# watchplb_mainboard_v1_1.net
KiCad netlist of a schematic drawn in EAGLE
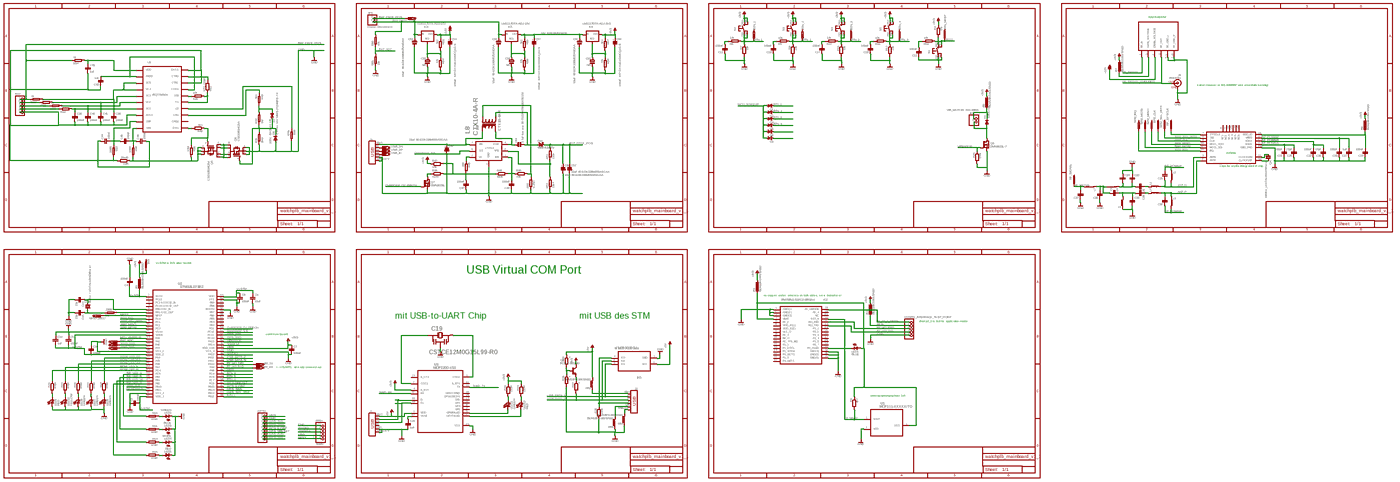
[diagram p0: schematic, sheet 1, overview]
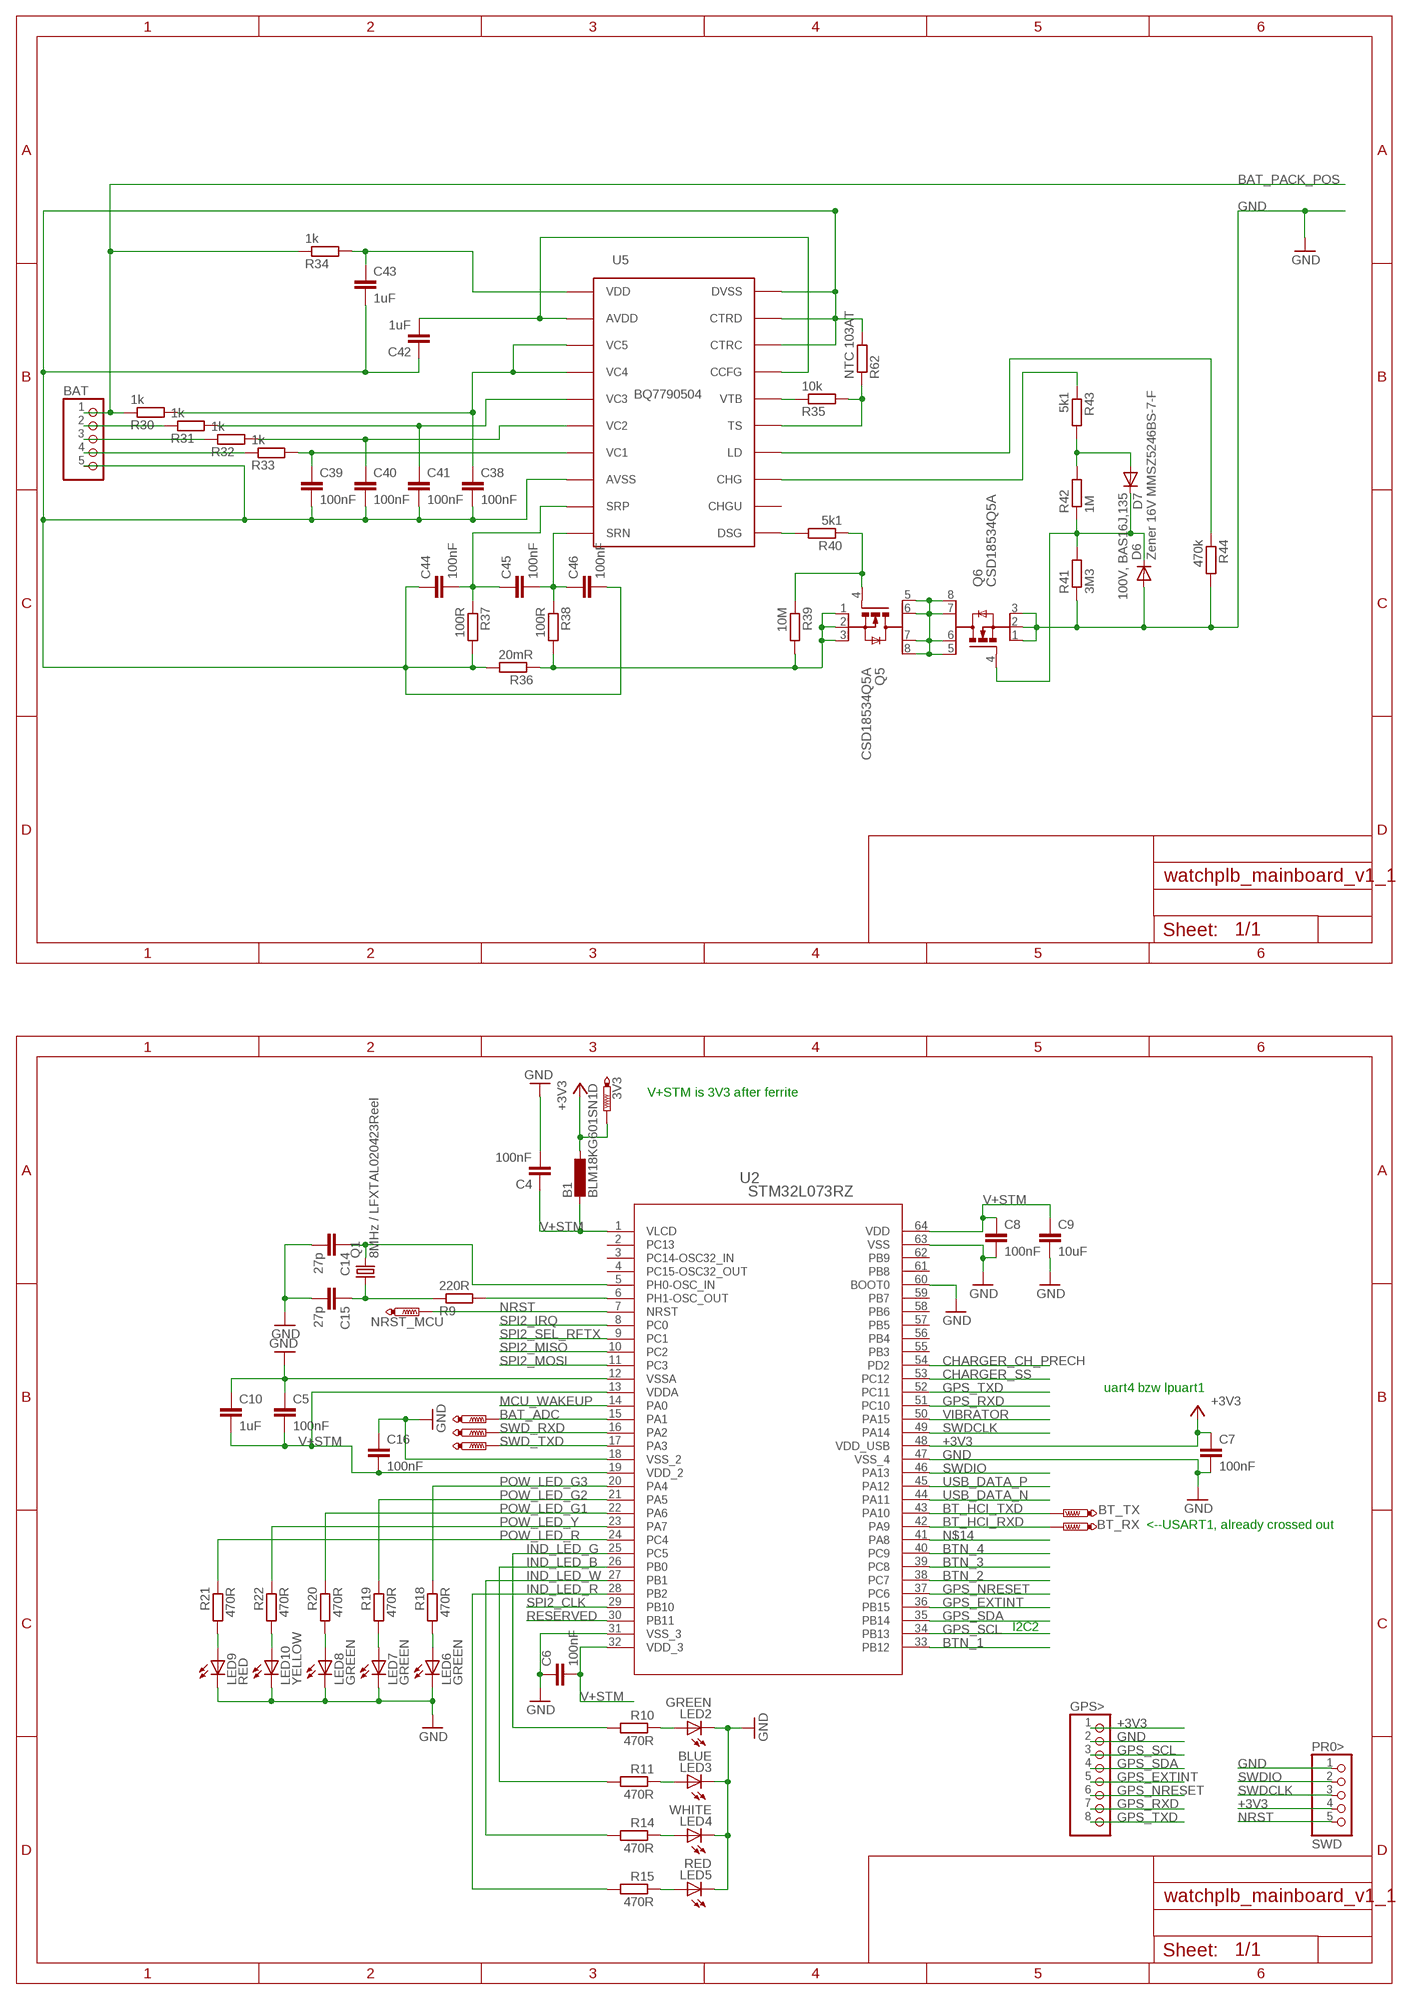
[diagram p1: schematic, sheet 1, part 1 of 4]
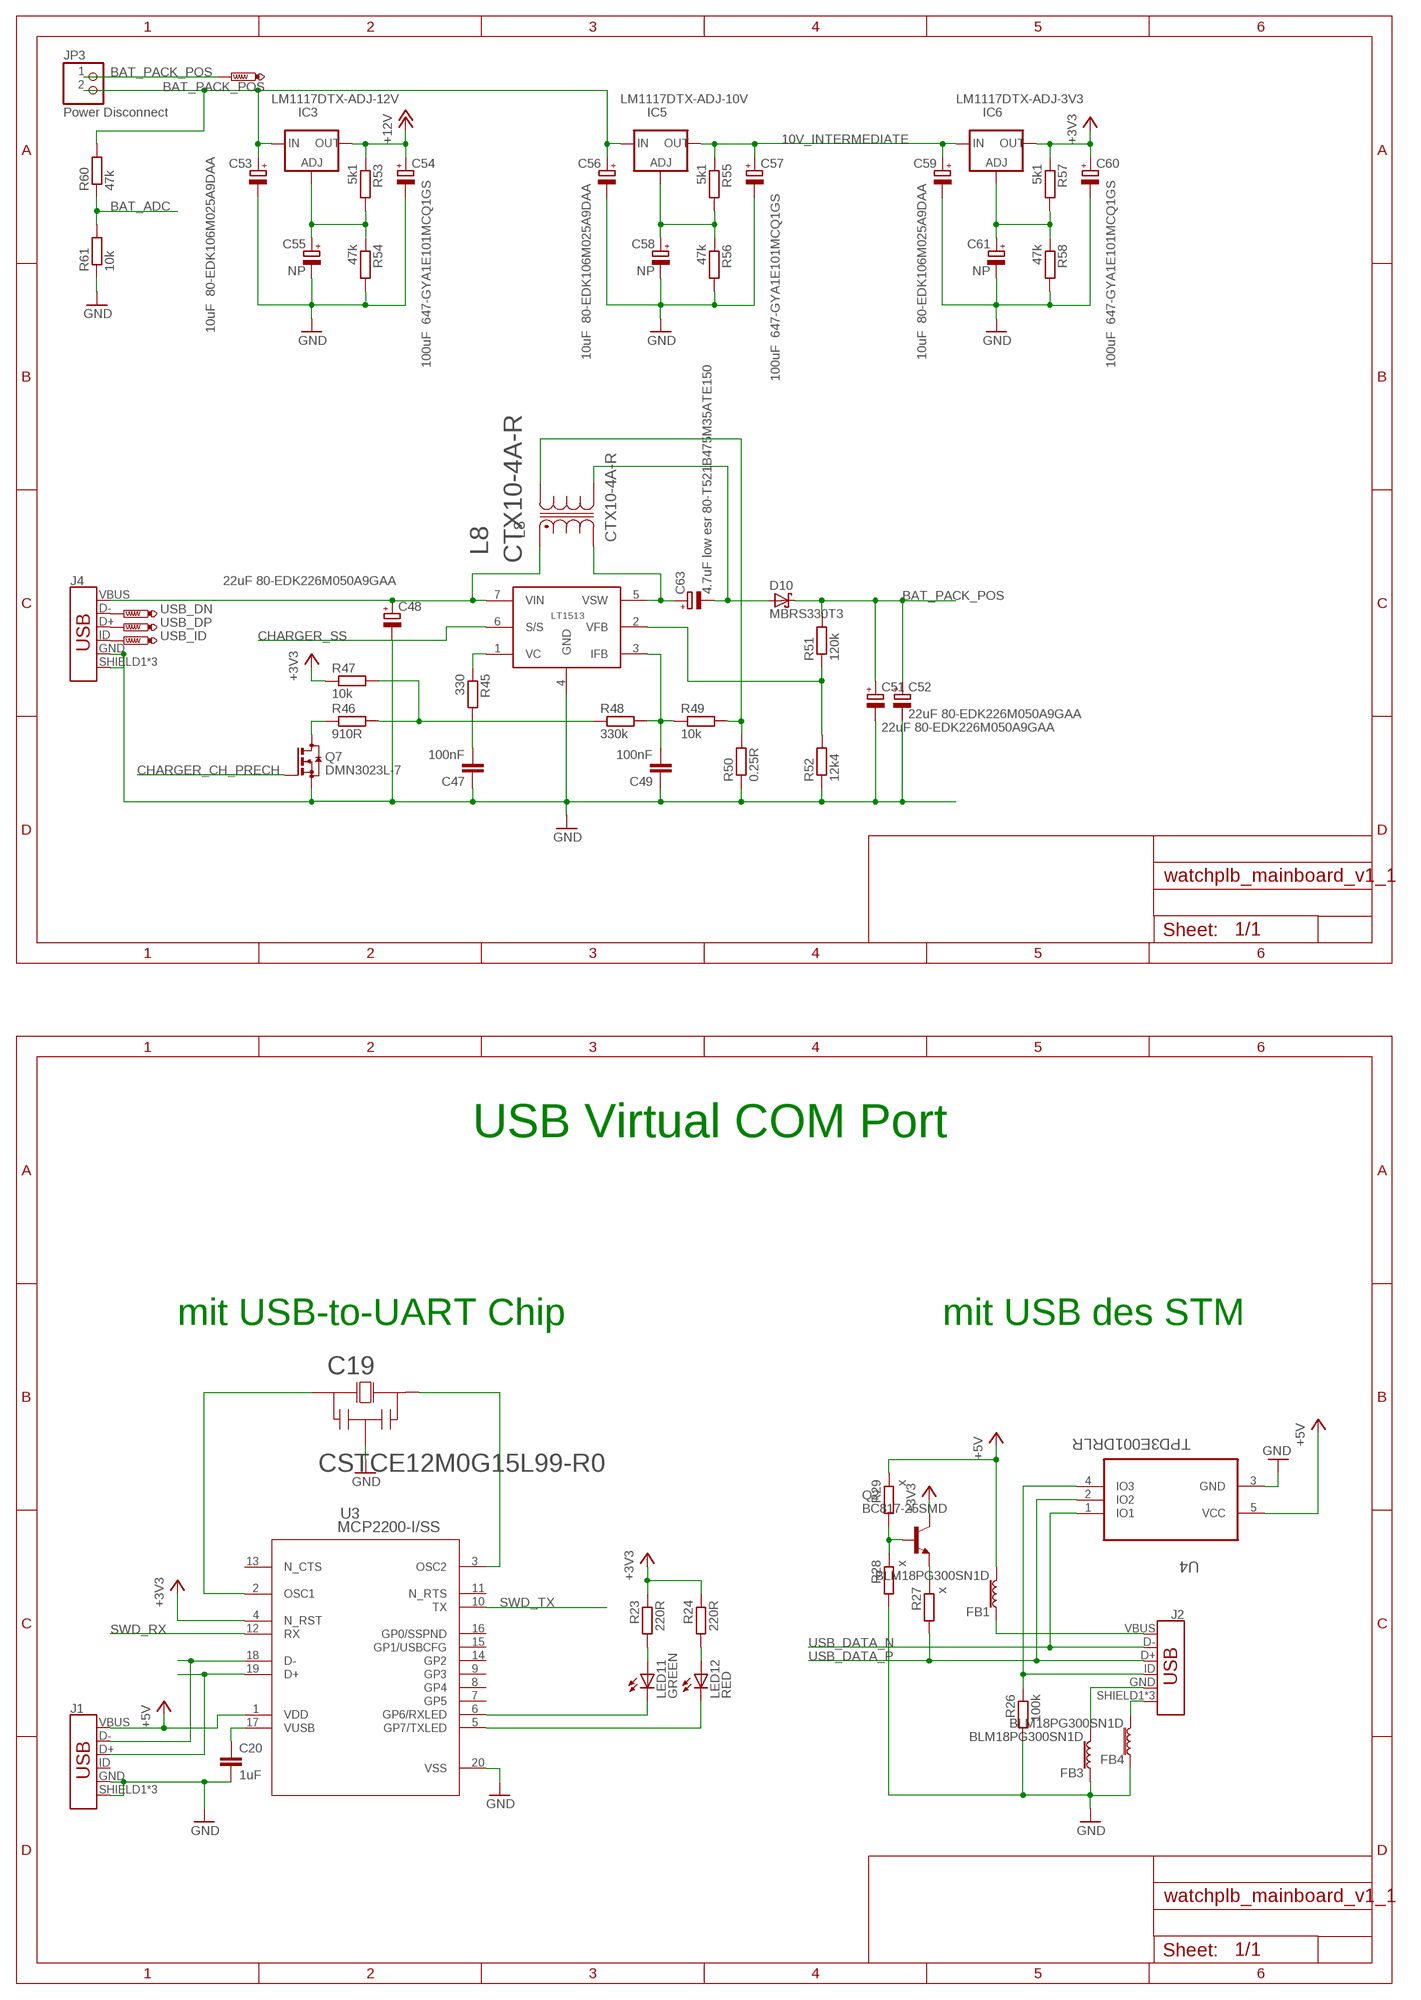
[diagram p2: schematic, sheet 1, part 2 of 4]
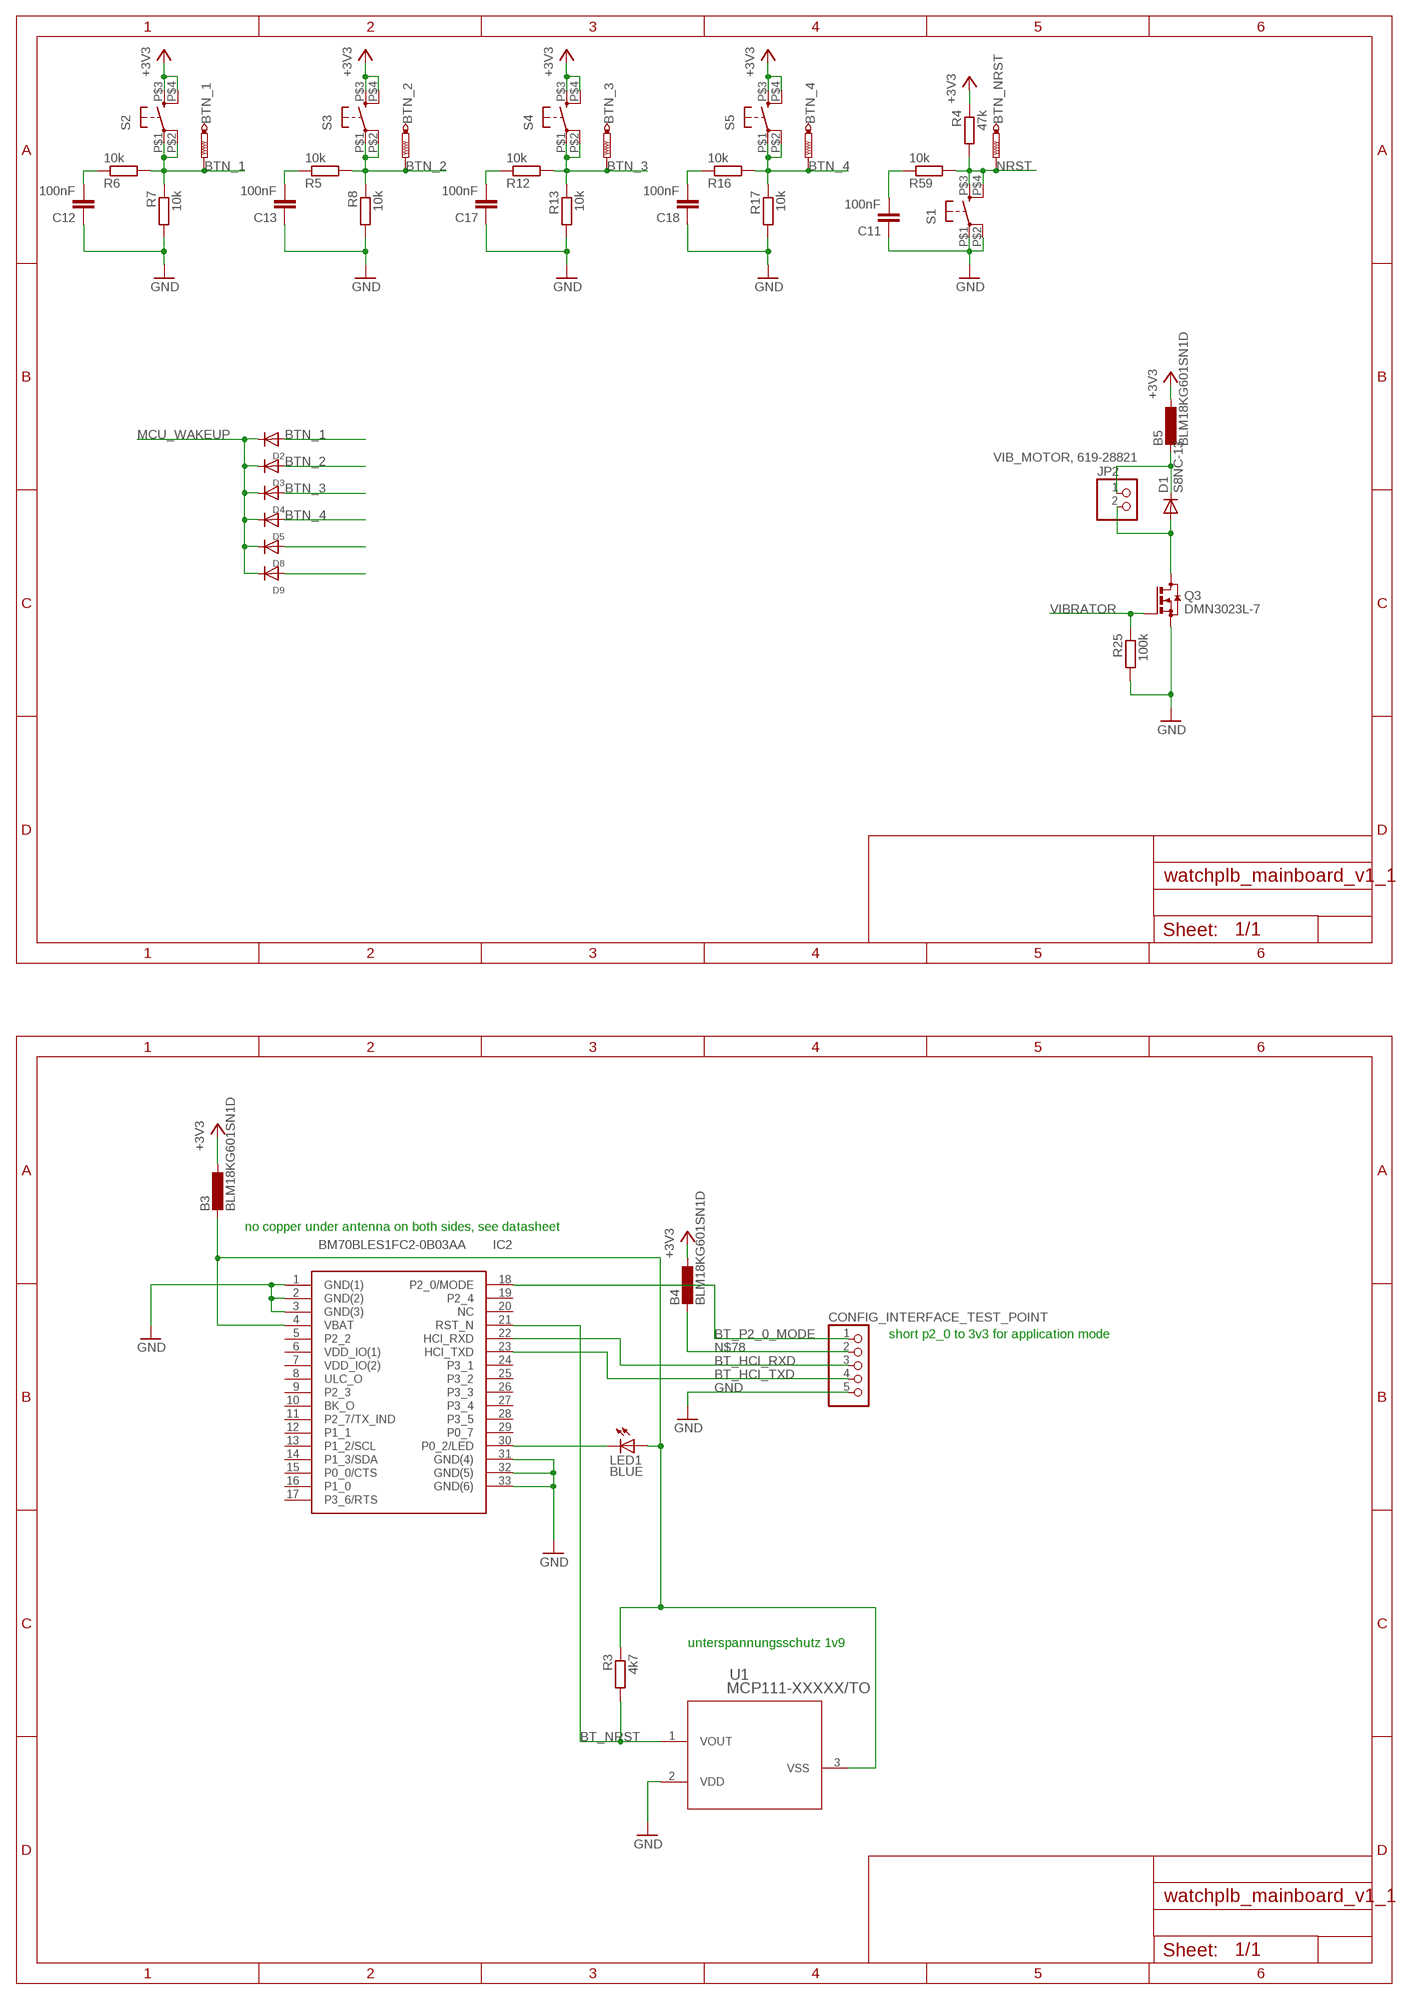
[diagram p3: schematic, sheet 1, part 3 of 4]
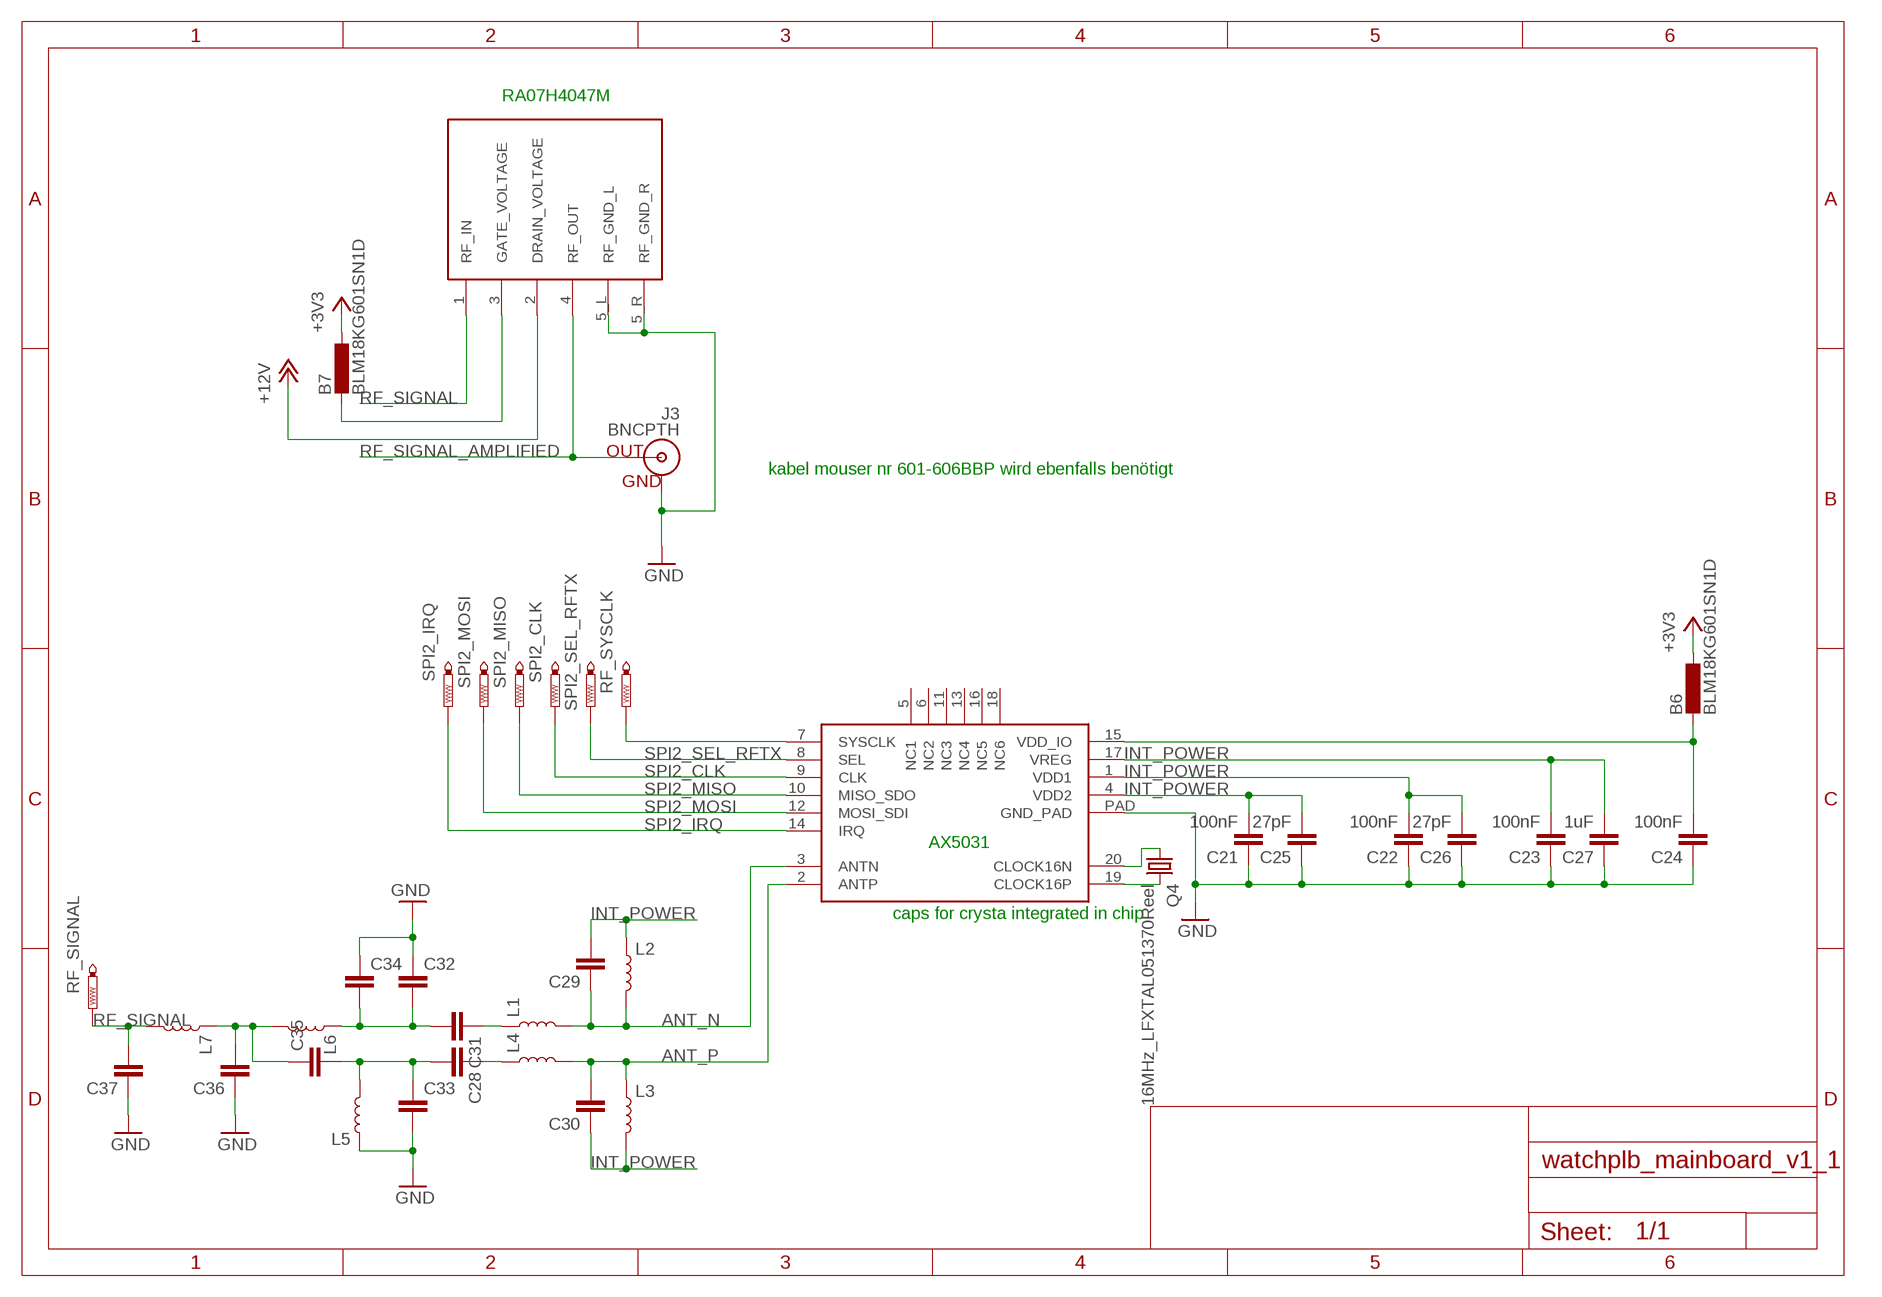
[diagram p4: schematic, sheet 1, part 4 of 4]

(export (version "E")
  (design (tool "Eeschema 10.0.6"))
  (components
    (comp (ref "3V3")
      (value "PTR1B1,27")
      (footprint "eagle-import:B1,27")
      (libsource (lib "eagle-import") (part "PTR1B1,27"))
    )
    (comp (ref "B1")
      (value "BLM18KG601SN1D")
      (footprint "eagle-import:L0603")
      (libsource (lib "eagle-import") (part "B-EU_B0603"))
    )
    (comp (ref "B3")
      (value "BLM18KG601SN1D")
      (footprint "eagle-import:L0603")
      (libsource (lib "eagle-import") (part "B-EU_B0603"))
    )
    (comp (ref "B4")
      (value "BLM18KG601SN1D")
      (footprint "eagle-import:L0603")
      (libsource (lib "eagle-import") (part "B-EU_B0603"))
    )
    (comp (ref "B5")
      (value "BLM18KG601SN1D")
      (footprint "eagle-import:L0603")
      (libsource (lib "eagle-import") (part "B-EU_B0603"))
    )
    (comp (ref "B6")
      (value "BLM18KG601SN1D")
      (footprint "eagle-import:L0603")
      (libsource (lib "eagle-import") (part "B-EU_B0603"))
    )
    (comp (ref "B7")
      (value "BLM18KG601SN1D")
      (footprint "eagle-import:L0603")
      (libsource (lib "eagle-import") (part "B-EU_B0603"))
    )
    (comp (ref "BAT")
      (value "PINHD-1X5")
      (footprint "eagle-import:1X05")
      (libsource (lib "eagle-import") (part "PINHD-1X5"))
    )
    (comp (ref "BAT_ADC")
      (value "PTR1B1,27")
      (footprint "eagle-import:B1,27")
      (libsource (lib "eagle-import") (part "PTR1B1,27"))
    )
    (comp (ref "BAT_PACK_POS")
      (value "PTR1B2,54")
      (footprint "eagle-import:B2,54")
      (libsource (lib "eagle-import") (part "PTR1B2,54"))
    )
    (comp (ref "BTN_1")
      (value "PTR1B1,27")
      (footprint "eagle-import:B1,27")
      (libsource (lib "eagle-import") (part "PTR1B1,27"))
    )
    (comp (ref "BTN_2")
      (value "PTR1B1,27")
      (footprint "eagle-import:B1,27")
      (libsource (lib "eagle-import") (part "PTR1B1,27"))
    )
    (comp (ref "BTN_3")
      (value "PTR1B1,27")
      (footprint "eagle-import:B1,27")
      (libsource (lib "eagle-import") (part "PTR1B1,27"))
    )
    (comp (ref "BTN_4")
      (value "PTR1B1,27")
      (footprint "eagle-import:B1,27")
      (libsource (lib "eagle-import") (part "PTR1B1,27"))
    )
    (comp (ref "BTN_NRST")
      (value "PTR1B1,27")
      (footprint "eagle-import:B1,27")
      (libsource (lib "eagle-import") (part "PTR1B1,27"))
    )
    (comp (ref "BT_RX")
      (value "PTR1B1,27")
      (footprint "eagle-import:B1,27")
      (libsource (lib "eagle-import") (part "PTR1B1,27"))
    )
    (comp (ref "BT_TX")
      (value "PTR1B1,27")
      (footprint "eagle-import:B1,27")
      (libsource (lib "eagle-import") (part "PTR1B1,27"))
    )
    (comp (ref "C4")
      (value "100nF")
      (footprint "eagle-import:C0805")
      (libsource (lib "eagle-import") (part "C-EUC0805"))
    )
    (comp (ref "C5")
      (value "100nF")
      (footprint "eagle-import:C0805")
      (libsource (lib "eagle-import") (part "C-EUC0805"))
    )
    (comp (ref "C6")
      (value "100nF")
      (footprint "eagle-import:C0805")
      (libsource (lib "eagle-import") (part "C-EUC0805"))
    )
    (comp (ref "C7")
      (value "100nF")
      (footprint "eagle-import:C0805")
      (libsource (lib "eagle-import") (part "C-EUC0805"))
    )
    (comp (ref "C8")
      (value "100nF")
      (footprint "eagle-import:C0805")
      (libsource (lib "eagle-import") (part "C-EUC0805"))
    )
    (comp (ref "C9")
      (value "10uF")
      (footprint "eagle-import:C1206")
      (libsource (lib "eagle-import") (part "C-EUC1206"))
    )
    (comp (ref "C10")
      (value "1uF")
      (footprint "eagle-import:C0805")
      (libsource (lib "eagle-import") (part "C-EUC0805"))
    )
    (comp (ref "C11")
      (value "100nF")
      (footprint "eagle-import:C0805")
      (libsource (lib "eagle-import") (part "C-EUC0805"))
    )
    (comp (ref "C12")
      (value "100nF")
      (footprint "eagle-import:C0805")
      (libsource (lib "eagle-import") (part "C-EUC0805"))
    )
    (comp (ref "C13")
      (value "100nF")
      (footprint "eagle-import:C0805")
      (libsource (lib "eagle-import") (part "C-EUC0805"))
    )
    (comp (ref "C14")
      (value "27p")
      (footprint "eagle-import:C0805")
      (libsource (lib "eagle-import") (part "C-EUC0805"))
    )
    (comp (ref "C15")
      (value "27p")
      (footprint "eagle-import:C0805")
      (libsource (lib "eagle-import") (part "C-EUC0805"))
    )
    (comp (ref "C16")
      (value "100nF")
      (footprint "eagle-import:C0805")
      (libsource (lib "eagle-import") (part "C-EUC0805"))
    )
    (comp (ref "C17")
      (value "100nF")
      (footprint "eagle-import:C0805")
      (libsource (lib "eagle-import") (part "C-EUC0805"))
    )
    (comp (ref "C18")
      (value "100nF")
      (footprint "eagle-import:C0805")
      (libsource (lib "eagle-import") (part "C-EUC0805"))
    )
    (comp (ref "C19")
      (value "CSTCE12M0G15L99-R0")
      (footprint "eagle-import:CSTCE")
      (fields (field (name "MANUFACTURER_PART_NUMBER") "CSTCE8M00G52R0"))
      (libsource (lib "eagle-import") (part "CSTCE8M00G52-R0"))
    )
    (comp (ref "C20")
      (value "1uF")
      (footprint "eagle-import:C0805")
      (libsource (lib "eagle-import") (part "C-EUC0805"))
    )
    (comp (ref "C21")
      (value "100nF")
      (footprint "eagle-import:C0805")
      (libsource (lib "eagle-import") (part "C-EUC0805"))
    )
    (comp (ref "C22")
      (value "100nF")
      (footprint "eagle-import:C0805")
      (libsource (lib "eagle-import") (part "C-EUC0805"))
    )
    (comp (ref "C23")
      (value "100nF")
      (footprint "eagle-import:C0805")
      (libsource (lib "eagle-import") (part "C-EUC0805"))
    )
    (comp (ref "C24")
      (value "100nF")
      (footprint "eagle-import:C0805")
      (libsource (lib "eagle-import") (part "C-EUC0805"))
    )
    (comp (ref "C25")
      (value "27pF")
      (footprint "eagle-import:C0805")
      (libsource (lib "eagle-import") (part "C-EUC0805"))
    )
    (comp (ref "C26")
      (value "27pF")
      (footprint "eagle-import:C0805")
      (libsource (lib "eagle-import") (part "C-EUC0805"))
    )
    (comp (ref "C27")
      (value "1uF")
      (footprint "eagle-import:C0805")
      (libsource (lib "eagle-import") (part "C-EUC0805"))
    )
    (comp (ref "C28")
      (value "C-EUC0805")
      (footprint "eagle-import:C0805")
      (libsource (lib "eagle-import") (part "C-EUC0805"))
    )
    (comp (ref "C29")
      (value "C-EUC0805")
      (footprint "eagle-import:C0805")
      (libsource (lib "eagle-import") (part "C-EUC0805"))
    )
    (comp (ref "C30")
      (value "C-EUC0805")
      (footprint "eagle-import:C0805")
      (libsource (lib "eagle-import") (part "C-EUC0805"))
    )
    (comp (ref "C31")
      (value "C-EUC0805")
      (footprint "eagle-import:C0805")
      (libsource (lib "eagle-import") (part "C-EUC0805"))
    )
    (comp (ref "C32")
      (value "C-EUC0805")
      (footprint "eagle-import:C0805")
      (libsource (lib "eagle-import") (part "C-EUC0805"))
    )
    (comp (ref "C33")
      (value "C-EUC0805")
      (footprint "eagle-import:C0805")
      (libsource (lib "eagle-import") (part "C-EUC0805"))
    )
    (comp (ref "C34")
      (value "C-EUC0805")
      (footprint "eagle-import:C0805")
      (libsource (lib "eagle-import") (part "C-EUC0805"))
    )
    (comp (ref "C35")
      (value "C-EUC0805")
      (footprint "eagle-import:C0805")
      (libsource (lib "eagle-import") (part "C-EUC0805"))
    )
    (comp (ref "C36")
      (value "C-EUC0805")
      (footprint "eagle-import:C0805")
      (libsource (lib "eagle-import") (part "C-EUC0805"))
    )
    (comp (ref "C37")
      (value "C-EUC0805")
      (footprint "eagle-import:C0805")
      (libsource (lib "eagle-import") (part "C-EUC0805"))
    )
    (comp (ref "C38")
      (value "100nF")
      (footprint "eagle-import:C0805K")
      (libsource (lib "eagle-import") (part "C-EUC0805K"))
    )
    (comp (ref "C39")
      (value "100nF")
      (footprint "eagle-import:C0805K")
      (libsource (lib "eagle-import") (part "C-EUC0805K"))
    )
    (comp (ref "C40")
      (value "100nF")
      (footprint "eagle-import:C0805K")
      (libsource (lib "eagle-import") (part "C-EUC0805K"))
    )
    (comp (ref "C41")
      (value "100nF")
      (footprint "eagle-import:C0805K")
      (libsource (lib "eagle-import") (part "C-EUC0805K"))
    )
    (comp (ref "C42")
      (value "1uF")
      (footprint "eagle-import:C0805K")
      (libsource (lib "eagle-import") (part "C-EUC0805K"))
    )
    (comp (ref "C43")
      (value "1uF")
      (footprint "eagle-import:C0805K")
      (libsource (lib "eagle-import") (part "C-EUC0805K"))
    )
    (comp (ref "C44")
      (value "100nF")
      (footprint "eagle-import:C0805K")
      (libsource (lib "eagle-import") (part "C-EUC0805K"))
    )
    (comp (ref "C45")
      (value "100nF")
      (footprint "eagle-import:C0805K")
      (libsource (lib "eagle-import") (part "C-EUC0805K"))
    )
    (comp (ref "C46")
      (value "100nF")
      (footprint "eagle-import:C0805K")
      (libsource (lib "eagle-import") (part "C-EUC0805K"))
    )
    (comp (ref "C47")
      (value "100nF")
      (footprint "eagle-import:C0805K")
      (libsource (lib "eagle-import") (part "C-EUC0805K"))
    )
    (comp (ref "C48")
      (value "22uF 80-EDK226M050A9GAA")
      (footprint "eagle-import:PANASONIC_E")
      (libsource (lib "eagle-import") (part "CPOL-EUE"))
    )
    (comp (ref "C49")
      (value "100nF")
      (footprint "eagle-import:C0805K")
      (libsource (lib "eagle-import") (part "C-EUC0805K"))
    )
    (comp (ref "C51")
      (value "22uF 80-EDK226M050A9GAA")
      (footprint "eagle-import:PANASONIC_E")
      (libsource (lib "eagle-import") (part "CPOL-EUE"))
    )
    (comp (ref "C52")
      (value "22uF 80-EDK226M050A9GAA")
      (footprint "eagle-import:PANASONIC_E")
      (libsource (lib "eagle-import") (part "CPOL-EUE"))
    )
    (comp (ref "C53")
      (value "10uF 80-EDK106M025A9DAA")
      (footprint "eagle-import:PANASONIC_E")
      (libsource (lib "eagle-import") (part "CPOL-EUE"))
    )
    (comp (ref "C54")
      (value "100uF 647-GYA1E101MCQ1GS")
      (footprint "eagle-import:PANASONIC_E")
      (libsource (lib "eagle-import") (part "CPOL-EUE"))
    )
    (comp (ref "C55")
      (value "NP")
      (footprint "eagle-import:PANASONIC_E")
      (libsource (lib "eagle-import") (part "CPOL-EUE"))
    )
    (comp (ref "C56")
      (value "10uF 80-EDK106M025A9DAA")
      (footprint "eagle-import:PANASONIC_E")
      (libsource (lib "eagle-import") (part "CPOL-EUE"))
    )
    (comp (ref "C57")
      (value "100uF 647-GYA1E101MCQ1GS")
      (footprint "eagle-import:PANASONIC_E")
      (libsource (lib "eagle-import") (part "CPOL-EUE"))
    )
    (comp (ref "C58")
      (value "NP")
      (footprint "eagle-import:PANASONIC_E")
      (libsource (lib "eagle-import") (part "CPOL-EUE"))
    )
    (comp (ref "C59")
      (value "10uF 80-EDK106M025A9DAA")
      (footprint "eagle-import:PANASONIC_E")
      (libsource (lib "eagle-import") (part "CPOL-EUE"))
    )
    (comp (ref "C60")
      (value "100uF 647-GYA1E101MCQ1GS")
      (footprint "eagle-import:PANASONIC_E")
      (libsource (lib "eagle-import") (part "CPOL-EUE"))
    )
    (comp (ref "C61")
      (value "NP")
      (footprint "eagle-import:PANASONIC_E")
      (libsource (lib "eagle-import") (part "CPOL-EUE"))
    )
    (comp (ref "C63")
      (value "4.7uF low esr 80-T521B475M35ATE150")
      (footprint "eagle-import:B_3528-21R")
      (libsource (lib "eagle-import") (part "CPOL-EUB/3528-21R"))
    )
    (comp (ref "CONFIG_INTERFACE_TEST_POINT")
      (value "PINHD-1X5")
      (footprint "eagle-import:1X05")
      (libsource (lib "eagle-import") (part "PINHD-1X5"))
    )
    (comp (ref "D1")
      (value "S8NC-13")
      (footprint "eagle-import:SMC")
      (libsource (lib "eagle-import") (part "DIODE-SMC"))
    )
    (comp (ref "D2")
      (value "DIODESOD-123")
      (footprint "eagle-import:SOD-123")
      (libsource (lib "eagle-import") (part "DIODESOD-123"))
    )
    (comp (ref "D3")
      (value "DIODESOD-123")
      (footprint "eagle-import:SOD-123")
      (libsource (lib "eagle-import") (part "DIODESOD-123"))
    )
    (comp (ref "D4")
      (value "DIODESOD-123")
      (footprint "eagle-import:SOD-123")
      (libsource (lib "eagle-import") (part "DIODESOD-123"))
    )
    (comp (ref "D5")
      (value "DIODESOD-123")
      (footprint "eagle-import:SOD-123")
      (libsource (lib "eagle-import") (part "DIODESOD-123"))
    )
    (comp (ref "D6")
      (value "Zener 16V MMSZ5246BS-7-F")
      (footprint "eagle-import:SOD323-R")
      (libsource (lib "eagle-import") (part "diode-1_DIODE-SOD323-R"))
    )
    (comp (ref "D7")
      (value "100V, BAS16J,135")
      (footprint "eagle-import:SOD323-R")
      (libsource (lib "eagle-import") (part "diode-1_DIODE-SOD323-R"))
    )
    (comp (ref "D8")
      (value "DIODESOD-123")
      (footprint "eagle-import:SOD-123")
      (libsource (lib "eagle-import") (part "DIODESOD-123"))
    )
    (comp (ref "D9")
      (value "DIODESOD-123")
      (footprint "eagle-import:SOD-123")
      (libsource (lib "eagle-import") (part "DIODESOD-123"))
    )
    (comp (ref "D10")
      (value "MBRS330T3")
      (footprint "eagle-import:SMC")
      (libsource (lib "eagle-import") (part "MBRS30T33"))
    )
    (comp (ref "FB1")
      (value "BLM18PG300SN1D")
      (footprint "eagle-import:0603")
      (libsource (lib "eagle-import") (part "FERRITE_BEAD-0603"))
    )
    (comp (ref "FB3")
      (value "BLM18PG300SN1D")
      (footprint "eagle-import:0603")
      (libsource (lib "eagle-import") (part "FERRITE_BEAD-0603"))
    )
    (comp (ref "FB4")
      (value "BLM18PG300SN1D")
      (footprint "eagle-import:0603")
      (libsource (lib "eagle-import") (part "FERRITE_BEAD-0603"))
    )
    (comp (ref "GPS>")
      (value "PINHD-1X8")
      (footprint "eagle-import:1X08")
      (libsource (lib "eagle-import") (part "PINHD-1X8"))
    )
    (comp (ref "IC2")
      (value "BM70BLES1FC2-0B03AA")
      (footprint "eagle-import:BM78SPPS5NC2_1")
      (libsource (lib "eagle-import") (part "BM70BLES1FC2-0B03AA"))
    )
    (comp (ref "IC3")
      (value "LM1117DTX-ADJ-12V")
      (footprint "eagle-import:TO252")
      (libsource (lib "eagle-import") (part "LM1117DTX-ADJ"))
    )
    (comp (ref "IC5")
      (value "LM1117DTX-ADJ-10V")
      (footprint "eagle-import:TO252")
      (libsource (lib "eagle-import") (part "LM1117DTX-ADJ"))
    )
    (comp (ref "IC6")
      (value "LM1117DTX-ADJ-3V3")
      (footprint "eagle-import:TO252")
      (libsource (lib "eagle-import") (part "LM1117DTX-ADJ"))
    )
    (comp (ref "J1")
      (value "USB_MICRO-B_FEMALE-SMT")
      (footprint "eagle-import:USB-B-MICRO-SMD")
      (libsource (lib "eagle-import") (part "USB_MICRO-B_FEMALE-SMT"))
    )
    (comp (ref "J2")
      (value "USB_MICRO-B_FEMALE-SMT")
      (footprint "eagle-import:USB-B-MICRO-SMD")
      (libsource (lib "eagle-import") (part "USB_MICRO-B_FEMALE-SMT"))
    )
    (comp (ref "J3")
      (value "BNCPTH")
      (footprint "eagle-import:BNC")
      (libsource (lib "eagle-import") (part "BNCPTH"))
    )
    (comp (ref "J4")
      (value "USB_MICRO-B_FEMALE-SMT")
      (footprint "eagle-import:USB-B-MICRO-SMD")
      (libsource (lib "eagle-import") (part "USB_MICRO-B_FEMALE-SMT"))
    )
    (comp (ref "JP2")
      (value "VIB_MOTOR, 619-28821")
      (footprint "eagle-import:1X02")
      (libsource (lib "eagle-import") (part "PINHD-1X2"))
    )
    (comp (ref "JP3")
      (value "Power Disconnect")
      (footprint "eagle-import:1X02")
      (libsource (lib "eagle-import") (part "PINHD-1X2"))
    )
    (comp (ref "L1")
      (value "INDUCTOR-0805-3.3UH")
      (footprint "eagle-import:0805")
      (libsource (lib "eagle-import") (part "INDUCTOR-0805-3.3UH"))
    )
    (comp (ref "L2")
      (value "INDUCTOR-0805-3.3UH")
      (footprint "eagle-import:0805")
      (libsource (lib "eagle-import") (part "INDUCTOR-0805-3.3UH"))
    )
    (comp (ref "L3")
      (value "INDUCTOR-0805-3.3UH")
      (footprint "eagle-import:0805")
      (libsource (lib "eagle-import") (part "INDUCTOR-0805-3.3UH"))
    )
    (comp (ref "L4")
      (value "INDUCTOR-0805-3.3UH")
      (footprint "eagle-import:0805")
      (libsource (lib "eagle-import") (part "INDUCTOR-0805-3.3UH"))
    )
    (comp (ref "L5")
      (value "INDUCTOR-0805-3.3UH")
      (footprint "eagle-import:0805")
      (libsource (lib "eagle-import") (part "INDUCTOR-0805-3.3UH"))
    )
    (comp (ref "L6")
      (value "INDUCTOR-0805-3.3UH")
      (footprint "eagle-import:0805")
      (libsource (lib "eagle-import") (part "INDUCTOR-0805-3.3UH"))
    )
    (comp (ref "L7")
      (value "INDUCTOR-0805-3.3UH")
      (footprint "eagle-import:0805")
      (libsource (lib "eagle-import") (part "INDUCTOR-0805-3.3UH"))
    )
    (comp (ref "L8")
      (value "CTX10-4A-R")
      (footprint "eagle-import:INDM115115X635N")
      (fields (field (name "MF") "Eaton"))
      (libsource (lib "eagle-import") (part "CTX10-4A-R"))
    )
    (comp (ref "LED1")
      (value "BLUE")
      (footprint "eagle-import:CHIP-LED0805")
      (libsource (lib "eagle-import") (part "LEDCHIP-LED0805"))
    )
    (comp (ref "LED2")
      (value "GREEN")
      (footprint "eagle-import:CHIP-LED0805")
      (libsource (lib "eagle-import") (part "LEDCHIP-LED0805"))
    )
    (comp (ref "LED3")
      (value "BLUE")
      (footprint "eagle-import:CHIP-LED0805")
      (libsource (lib "eagle-import") (part "LEDCHIP-LED0805"))
    )
    (comp (ref "LED4")
      (value "WHITE")
      (footprint "eagle-import:CHIP-LED0805")
      (libsource (lib "eagle-import") (part "LEDCHIP-LED0805"))
    )
    (comp (ref "LED5")
      (value "RED")
      (footprint "eagle-import:CHIP-LED0805")
      (libsource (lib "eagle-import") (part "LEDCHIP-LED0805"))
    )
    (comp (ref "LED6")
      (value "GREEN")
      (footprint "eagle-import:CHIP-LED0805")
      (libsource (lib "eagle-import") (part "LEDCHIP-LED0805"))
    )
    (comp (ref "LED7")
      (value "GREEN")
      (footprint "eagle-import:CHIP-LED0805")
      (libsource (lib "eagle-import") (part "LEDCHIP-LED0805"))
    )
    (comp (ref "LED8")
      (value "GREEN")
      (footprint "eagle-import:CHIP-LED0805")
      (libsource (lib "eagle-import") (part "LEDCHIP-LED0805"))
    )
    (comp (ref "LED9")
      (value "RED")
      (footprint "eagle-import:CHIP-LED0805")
      (libsource (lib "eagle-import") (part "LEDCHIP-LED0805"))
    )
    (comp (ref "LED10")
      (value "YELLOW")
      (footprint "eagle-import:CHIP-LED0805")
      (libsource (lib "eagle-import") (part "LEDCHIP-LED0805"))
    )
    (comp (ref "LED11")
      (value "GREEN")
      (footprint "eagle-import:CHIP-LED0805")
      (libsource (lib "eagle-import") (part "LEDCHIP-LED0805"))
    )
    (comp (ref "LED12")
      (value "RED")
      (footprint "eagle-import:CHIP-LED0805")
      (libsource (lib "eagle-import") (part "LEDCHIP-LED0805"))
    )
    (comp (ref "NRST_MCU")
      (value "PTR1B1,27")
      (footprint "eagle-import:B1,27")
      (libsource (lib "eagle-import") (part "PTR1B1,27"))
    )
    (comp (ref "PR0>")
      (value "SWD")
      (footprint "eagle-import:1X05")
      (libsource (lib "eagle-import") (part "PINHD-1X5"))
    )
    (comp (ref "Q1")
      (value "8MHz / LFXTAL020423Reel")
      (footprint "eagle-import:HC49UP")
      (libsource (lib "eagle-import") (part "crystal_CRYSTALHC49UP"))
    )
    (comp (ref "Q2")
      (value "BC817-25SMD")
      (footprint "eagle-import:SOT23-BEC")
      (libsource (lib "eagle-import") (part "BC817SMD-25"))
    )
    (comp (ref "Q3")
      (value "DMN3023L-7")
      (footprint "eagle-import:SOT23")
      (libsource (lib "eagle-import") (part "BSS123"))
    )
    (comp (ref "Q4")
      (value "16MHz_LFXTAL051370Reel")
      (footprint "eagle-import:HC49UP")
      (libsource (lib "eagle-import") (part "CRYSTALHC49UP"))
    )
    (comp (ref "Q5")
      (value "CSD18534Q5A")
      (footprint "eagle-import:TRANS_CSD18534Q5A")
      (fields (field (name "MF") "Texas Instruments"))
      (libsource (lib "eagle-import") (part "CSD18534Q5A"))
    )
    (comp (ref "Q6")
      (value "CSD18534Q5A")
      (footprint "eagle-import:TRANS_CSD18534Q5A")
      (fields (field (name "MF") "Texas Instruments"))
      (libsource (lib "eagle-import") (part "CSD18534Q5A"))
    )
    (comp (ref "Q7")
      (value "DMN3023L-7")
      (footprint "eagle-import:SOT23")
      (libsource (lib "eagle-import") (part "BSS123"))
    )
    (comp (ref "R3")
      (value "4k7")
      (footprint "eagle-import:M0805")
      (libsource (lib "eagle-import") (part "R-EU_M0805"))
    )
    (comp (ref "R4")
      (value "47k")
      (footprint "eagle-import:M0805")
      (libsource (lib "eagle-import") (part "R-EU_M0805"))
    )
    (comp (ref "R5")
      (value "10k")
      (footprint "eagle-import:M0805")
      (libsource (lib "eagle-import") (part "R-EU_M0805"))
    )
    (comp (ref "R6")
      (value "10k")
      (footprint "eagle-import:M0805")
      (libsource (lib "eagle-import") (part "R-EU_M0805"))
    )
    (comp (ref "R7")
      (value "10k")
      (footprint "eagle-import:M0805")
      (libsource (lib "eagle-import") (part "R-EU_M0805"))
    )
    (comp (ref "R8")
      (value "10k")
      (footprint "eagle-import:M0805")
      (libsource (lib "eagle-import") (part "R-EU_M0805"))
    )
    (comp (ref "R9")
      (value "220R")
      (footprint "eagle-import:M0805")
      (libsource (lib "eagle-import") (part "R-EU_M0805"))
    )
    (comp (ref "R10")
      (value "470R")
      (footprint "eagle-import:M0805")
      (libsource (lib "eagle-import") (part "R-EU_M0805"))
    )
    (comp (ref "R11")
      (value "470R")
      (footprint "eagle-import:M0805")
      (libsource (lib "eagle-import") (part "R-EU_M0805"))
    )
    (comp (ref "R12")
      (value "10k")
      (footprint "eagle-import:M0805")
      (libsource (lib "eagle-import") (part "R-EU_M0805"))
    )
    (comp (ref "R13")
      (value "10k")
      (footprint "eagle-import:M0805")
      (libsource (lib "eagle-import") (part "R-EU_M0805"))
    )
    (comp (ref "R14")
      (value "470R")
      (footprint "eagle-import:M0805")
      (libsource (lib "eagle-import") (part "R-EU_M0805"))
    )
    (comp (ref "R15")
      (value "470R")
      (footprint "eagle-import:M0805")
      (libsource (lib "eagle-import") (part "R-EU_M0805"))
    )
    (comp (ref "R16")
      (value "10k")
      (footprint "eagle-import:M0805")
      (libsource (lib "eagle-import") (part "R-EU_M0805"))
    )
    (comp (ref "R17")
      (value "10k")
      (footprint "eagle-import:M0805")
      (libsource (lib "eagle-import") (part "R-EU_M0805"))
    )
    (comp (ref "R18")
      (value "470R")
      (footprint "eagle-import:M0805")
      (libsource (lib "eagle-import") (part "R-EU_M0805"))
    )
    (comp (ref "R19")
      (value "470R")
      (footprint "eagle-import:M0805")
      (libsource (lib "eagle-import") (part "R-EU_M0805"))
    )
    (comp (ref "R20")
      (value "470R")
      (footprint "eagle-import:M0805")
      (libsource (lib "eagle-import") (part "R-EU_M0805"))
    )
    (comp (ref "R21")
      (value "470R")
      (footprint "eagle-import:M0805")
      (libsource (lib "eagle-import") (part "R-EU_M0805"))
    )
    (comp (ref "R22")
      (value "470R")
      (footprint "eagle-import:M0805")
      (libsource (lib "eagle-import") (part "R-EU_M0805"))
    )
    (comp (ref "R23")
      (value "220R")
      (footprint "eagle-import:M0805")
      (libsource (lib "eagle-import") (part "R-EU_M0805"))
    )
    (comp (ref "R24")
      (value "220R")
      (footprint "eagle-import:M0805")
      (libsource (lib "eagle-import") (part "R-EU_M0805"))
    )
    (comp (ref "R25")
      (value "100k")
      (footprint "eagle-import:M0805")
      (libsource (lib "eagle-import") (part "R-EU_M0805"))
    )
    (comp (ref "R26")
      (value "100k")
      (footprint "eagle-import:M0805")
      (libsource (lib "eagle-import") (part "R-EU_M0805"))
    )
    (comp (ref "R27")
      (value "x")
      (footprint "eagle-import:M0805")
      (libsource (lib "eagle-import") (part "R-EU_M0805"))
    )
    (comp (ref "R28")
      (value "x")
      (footprint "eagle-import:M0805")
      (libsource (lib "eagle-import") (part "R-EU_M0805"))
    )
    (comp (ref "R29")
      (value "x")
      (footprint "eagle-import:M0805")
      (libsource (lib "eagle-import") (part "R-EU_M0805"))
    )
    (comp (ref "R30")
      (value "1k")
      (footprint "eagle-import:M0805")
      (libsource (lib "eagle-import") (part "R-EU_M0805"))
    )
    (comp (ref "R31")
      (value "1k")
      (footprint "eagle-import:M0805")
      (libsource (lib "eagle-import") (part "R-EU_M0805"))
    )
    (comp (ref "R32")
      (value "1k")
      (footprint "eagle-import:M0805")
      (libsource (lib "eagle-import") (part "R-EU_M0805"))
    )
    (comp (ref "R33")
      (value "1k")
      (footprint "eagle-import:M0805")
      (libsource (lib "eagle-import") (part "R-EU_M0805"))
    )
    (comp (ref "R34")
      (value "1k")
      (footprint "eagle-import:M0805")
      (libsource (lib "eagle-import") (part "R-EU_M0805"))
    )
    (comp (ref "R35")
      (value "10k")
      (footprint "eagle-import:M0805")
      (libsource (lib "eagle-import") (part "R-EU_M0805"))
    )
    (comp (ref "R36")
      (value "20mR")
      (footprint "eagle-import:R2512")
      (libsource (lib "eagle-import") (part "R-EU_R2512"))
    )
    (comp (ref "R37")
      (value "100R")
      (footprint "eagle-import:M0805")
      (libsource (lib "eagle-import") (part "R-EU_M0805"))
    )
    (comp (ref "R38")
      (value "100R")
      (footprint "eagle-import:M0805")
      (libsource (lib "eagle-import") (part "R-EU_M0805"))
    )
    (comp (ref "R39")
      (value "10M")
      (footprint "eagle-import:M0805")
      (libsource (lib "eagle-import") (part "R-EU_M0805"))
    )
    (comp (ref "R40")
      (value "5k1")
      (footprint "eagle-import:M0805")
      (libsource (lib "eagle-import") (part "R-EU_M0805"))
    )
    (comp (ref "R41")
      (value "3M3")
      (footprint "eagle-import:M0805")
      (libsource (lib "eagle-import") (part "R-EU_M0805"))
    )
    (comp (ref "R42")
      (value "1M")
      (footprint "eagle-import:M0805")
      (libsource (lib "eagle-import") (part "R-EU_M0805"))
    )
    (comp (ref "R43")
      (value "5k1")
      (footprint "eagle-import:M0805")
      (libsource (lib "eagle-import") (part "R-EU_M0805"))
    )
    (comp (ref "R44")
      (value "470k")
      (footprint "eagle-import:M0805")
      (libsource (lib "eagle-import") (part "R-EU_M0805"))
    )
    (comp (ref "R45")
      (value "330")
      (footprint "eagle-import:M0805")
      (libsource (lib "eagle-import") (part "R-EU_M0805"))
    )
    (comp (ref "R46")
      (value "910R")
      (footprint "eagle-import:M0805")
      (libsource (lib "eagle-import") (part "R-EU_M0805"))
    )
    (comp (ref "R47")
      (value "10k")
      (footprint "eagle-import:M0805")
      (libsource (lib "eagle-import") (part "R-EU_M0805"))
    )
    (comp (ref "R48")
      (value "330k")
      (footprint "eagle-import:M0805")
      (libsource (lib "eagle-import") (part "R-EU_M0805"))
    )
    (comp (ref "R49")
      (value "10k")
      (footprint "eagle-import:M0805")
      (libsource (lib "eagle-import") (part "R-EU_M0805"))
    )
    (comp (ref "R50")
      (value "0.25R")
      (footprint "eagle-import:R2512")
      (libsource (lib "eagle-import") (part "R-EU_R2512"))
    )
    (comp (ref "R51")
      (value "120k")
      (footprint "eagle-import:M0805")
      (libsource (lib "eagle-import") (part "R-EU_M0805"))
    )
    (comp (ref "R52")
      (value "12k4")
      (footprint "eagle-import:M0805")
      (libsource (lib "eagle-import") (part "R-EU_M0805"))
    )
    (comp (ref "R53")
      (value "5k1")
      (footprint "eagle-import:M0805")
      (libsource (lib "eagle-import") (part "R-EU_M0805"))
    )
    (comp (ref "R54")
      (value "47k")
      (footprint "eagle-import:M0805")
      (libsource (lib "eagle-import") (part "R-EU_M0805"))
    )
    (comp (ref "R55")
      (value "5k1")
      (footprint "eagle-import:M0805")
      (libsource (lib "eagle-import") (part "R-EU_M0805"))
    )
    (comp (ref "R56")
      (value "47k")
      (footprint "eagle-import:M0805")
      (libsource (lib "eagle-import") (part "R-EU_M0805"))
    )
    (comp (ref "R57")
      (value "5k1")
      (footprint "eagle-import:M0805")
      (libsource (lib "eagle-import") (part "R-EU_M0805"))
    )
    (comp (ref "R58")
      (value "47k")
      (footprint "eagle-import:M0805")
      (libsource (lib "eagle-import") (part "R-EU_M0805"))
    )
    (comp (ref "R59")
      (value "10k")
      (footprint "eagle-import:M0805")
      (libsource (lib "eagle-import") (part "R-EU_M0805"))
    )
    (comp (ref "R60")
      (value "47k")
      (footprint "eagle-import:M0805")
      (libsource (lib "eagle-import") (part "R-EU_M0805"))
    )
    (comp (ref "R61")
      (value "10k")
      (footprint "eagle-import:M0805")
      (libsource (lib "eagle-import") (part "R-EU_M0805"))
    )
    (comp (ref "R62")
      (value "NTC 103AT")
      (footprint "eagle-import:M0805")
      (libsource (lib "eagle-import") (part "R-EU_M0805"))
    )
    (comp (ref "RF_SIGNAL")
      (value "PTR1B2,54")
      (footprint "eagle-import:B2,54")
      (libsource (lib "eagle-import") (part "PTR1B2,54"))
    )
    (comp (ref "RF_SYSCLK")
      (value "PTR1B1,27")
      (footprint "eagle-import:B1,27")
      (libsource (lib "eagle-import") (part "PTR1B1,27"))
    )
    (comp (ref "S1")
      (value "TL3305")
      (footprint "eagle-import:SMD_SWITCH")
      (libsource (lib "eagle-import") (part "TL3305"))
    )
    (comp (ref "S2")
      (value "TL3305")
      (footprint "eagle-import:SMD_SWITCH")
      (libsource (lib "eagle-import") (part "TL3305"))
    )
    (comp (ref "S3")
      (value "TL3305")
      (footprint "eagle-import:SMD_SWITCH")
      (libsource (lib "eagle-import") (part "TL3305"))
    )
    (comp (ref "S4")
      (value "TL3305")
      (footprint "eagle-import:SMD_SWITCH")
      (libsource (lib "eagle-import") (part "TL3305"))
    )
    (comp (ref "S5")
      (value "TL3305")
      (footprint "eagle-import:SMD_SWITCH")
      (libsource (lib "eagle-import") (part "TL3305"))
    )
    (comp (ref "SPI2_CLK")
      (value "PTR1B1,27")
      (footprint "eagle-import:B1,27")
      (libsource (lib "eagle-import") (part "PTR1B1,27"))
    )
    (comp (ref "SPI2_IRQ")
      (value "PTR1B1,27")
      (footprint "eagle-import:B1,27")
      (libsource (lib "eagle-import") (part "PTR1B1,27"))
    )
    (comp (ref "SPI2_MISO")
      (value "PTR1B1,27")
      (footprint "eagle-import:B1,27")
      (libsource (lib "eagle-import") (part "PTR1B1,27"))
    )
    (comp (ref "SPI2_MOSI")
      (value "PTR1B1,27")
      (footprint "eagle-import:B1,27")
      (libsource (lib "eagle-import") (part "PTR1B1,27"))
    )
    (comp (ref "SPI2_SEL_RFTX")
      (value "PTR1B1,27")
      (footprint "eagle-import:B1,27")
      (libsource (lib "eagle-import") (part "PTR1B1,27"))
    )
    (comp (ref "SWD_RXD")
      (value "PTR1B1,27")
      (footprint "eagle-import:B1,27")
      (libsource (lib "eagle-import") (part "PTR1B1,27"))
    )
    (comp (ref "SWD_TXD")
      (value "PTR1B1,27")
      (footprint "eagle-import:B1,27")
      (libsource (lib "eagle-import") (part "PTR1B1,27"))
    )
    (comp (ref "U$1")
      (value "AX5031")
      (footprint "eagle-import:QFN20")
      (libsource (lib "eagle-import") (part "AX5031"))
    )
    (comp (ref "U$2")
      (value "RA07H4047M")
      (footprint "eagle-import:RA07H4047M")
      (libsource (lib "eagle-import") (part "RA07H4047M"))
    )
    (comp (ref "U$3")
      (value "LT1513")
      (footprint "eagle-import:TO220-7")
      (libsource (lib "eagle-import") (part "LT1513"))
    )
    (comp (ref "U1")
      (value "MCP111-XXXXX/TO")
      (footprint "eagle-import:TO-92_MC")
      (fields (field (name "MANUFACTURER_PART_NUMBER") "MCP111XXXXXTO"))
      (libsource (lib "eagle-import") (part "MCP111-XXXXX/TO"))
    )
    (comp (ref "U2")
      (value "STM32L073RZ")
      (footprint "eagle-import:LQFP64-10X10MM")
      (fields (field (name "MANUFACTURER_PART_NUMBER") "stm32l0x3rl"))
      (libsource (lib "eagle-import") (part "STM32L0X3RL"))
    )
    (comp (ref "U3")
      (value "MCP2200-I/SS")
      (footprint "eagle-import:SSOP20_MC")
      (fields (field (name "MANUFACTURER_PART_NUMBER") "mcp2200iss"))
      (libsource (lib "eagle-import") (part "MCP2200-I/SS"))
    )
    (comp (ref "U4")
      (value "TPD3E001DRLR")
      (footprint "eagle-import:SOT50P160X60-5N")
      (libsource (lib "eagle-import") (part "TPD3E001DRLR"))
    )
    (comp (ref "U5")
      (value "BQ7790504")
      (footprint "eagle-import:TSSOP-20_6MM")
      (libsource (lib "eagle-import") (part "BQ77904"))
    )
    (comp (ref "USB_DN")
      (value "PTR1B1,27")
      (footprint "eagle-import:B1,27")
      (libsource (lib "eagle-import") (part "PTR1B1,27"))
    )
    (comp (ref "USB_DP")
      (value "PTR1B1,27")
      (footprint "eagle-import:B1,27")
      (libsource (lib "eagle-import") (part "PTR1B1,27"))
    )
    (comp (ref "USB_ID")
      (value "PTR1B1,27")
      (footprint "eagle-import:B1,27")
      (libsource (lib "eagle-import") (part "PTR1B1,27"))
    )
  )
  (nets
    (net (code "1") (name "+3V3") (class "Default")
      (node (ref "3V3") (pin "TP") (pinfunction "TP_TP") (pintype "input"))
      (node (ref "B1") (pin "1") (pinfunction "1_1") (pintype "passive"))
      (node (ref "B3") (pin "1") (pinfunction "1_1") (pintype "passive"))
      (node (ref "B4") (pin "1") (pinfunction "1_1") (pintype "passive"))
      (node (ref "B5") (pin "1") (pinfunction "1_1") (pintype "passive"))
      (node (ref "B6") (pin "1") (pinfunction "1_1") (pintype "passive"))
      (node (ref "B7") (pin "1") (pinfunction "1_1") (pintype "passive"))
      (node (ref "C60") (pin "+") (pinfunction "+_+") (pintype "passive"))
      (node (ref "C7") (pin "1") (pinfunction "1_1") (pintype "passive"))
      (node (ref "GPS>") (pin "1") (pinfunction "1_1") (pintype "passive"))
      (node (ref "IC6") (pin "TAB") (pinfunction "OUT_TAB") (pintype "passive"))
      (node (ref "PR0>") (pin "4") (pinfunction "4_4") (pintype "passive"))
      (node (ref "Q2") (pin "C") (pinfunction "C_C") (pintype "passive"))
      (node (ref "R23") (pin "1") (pinfunction "1_1") (pintype "passive"))
      (node (ref "R24") (pin "1") (pinfunction "1_1") (pintype "passive"))
      (node (ref "R4") (pin "1") (pinfunction "1_1") (pintype "passive"))
      (node (ref "R47") (pin "1") (pinfunction "1_1") (pintype "passive"))
      (node (ref "R57") (pin "1") (pinfunction "1_1") (pintype "passive"))
      (node (ref "S2") (pin "P$3") (pinfunction "S_P$3") (pintype "passive"))
      (node (ref "S2") (pin "P$4") (pinfunction "S1_P$4") (pintype "passive"))
      (node (ref "S3") (pin "P$3") (pinfunction "S_P$3") (pintype "passive"))
      (node (ref "S3") (pin "P$4") (pinfunction "S1_P$4") (pintype "passive"))
      (node (ref "S4") (pin "P$3") (pinfunction "S_P$3") (pintype "passive"))
      (node (ref "S4") (pin "P$4") (pinfunction "S1_P$4") (pintype "passive"))
      (node (ref "S5") (pin "P$3") (pinfunction "S_P$3") (pintype "passive"))
      (node (ref "S5") (pin "P$4") (pinfunction "S1_P$4") (pintype "passive"))
      (node (ref "U2") (pin "48") (pinfunction "VDD_USB_48") (pintype "power_in"))
      (node (ref "U3") (pin "4") (pinfunction "N_RST_4") (pintype "input"))
    )
    (net (code "2") (name "+5V") (class "Default")
      (node (ref "FB1") (pin "2") (pinfunction "2_2") (pintype "passive"))
      (node (ref "J1") (pin "VBUS") (pinfunction "VBUS_VBUS") (pintype "power_in"))
      (node (ref "R29") (pin "1") (pinfunction "1_1") (pintype "passive"))
      (node (ref "U3") (pin "1") (pinfunction "VDD_1") (pintype "power_in"))
      (node (ref "U4") (pin "5") (pinfunction "VCC_5") (pintype "power_in"))
    )
    (net (code "3") (name "+12V") (class "Default")
      (node (ref "C54") (pin "+") (pinfunction "+_+") (pintype "passive"))
      (node (ref "IC3") (pin "TAB") (pinfunction "OUT_TAB") (pintype "passive"))
      (node (ref "R53") (pin "1") (pinfunction "1_1") (pintype "passive"))
      (node (ref "U$2") (pin "2") (pinfunction "DRAIN_VOLTAGE_2") (pintype "bidirectional"))
    )
    (net (code "4") (name "/10V_INTERMEDIATE") (class "Default")
      (node (ref "C57") (pin "+") (pinfunction "+_+") (pintype "passive"))
      (node (ref "C59") (pin "+") (pinfunction "+_+") (pintype "passive"))
      (node (ref "IC5") (pin "TAB") (pinfunction "OUT_TAB") (pintype "passive"))
      (node (ref "IC6") (pin "2") (pinfunction "IN_2") (pintype "input"))
      (node (ref "R55") (pin "1") (pinfunction "1_1") (pintype "passive"))
    )
    (net (code "5") (name "/ANT_N") (class "Default")
      (node (ref "C29") (pin "1") (pinfunction "1_1") (pintype "passive"))
      (node (ref "L1") (pin "2") (pinfunction "2_2") (pintype "passive"))
      (node (ref "L2") (pin "2") (pinfunction "2_2") (pintype "passive"))
      (node (ref "U$1") (pin "3") (pinfunction "ANTN_3") (pintype "output"))
    )
    (net (code "6") (name "/ANT_P") (class "Default")
      (node (ref "C30") (pin "2") (pinfunction "2_2") (pintype "passive"))
      (node (ref "L3") (pin "1") (pinfunction "1_1") (pintype "passive"))
      (node (ref "L4") (pin "2") (pinfunction "2_2") (pintype "passive"))
      (node (ref "U$1") (pin "2") (pinfunction "ANTP_2") (pintype "output"))
    )
    (net (code "7") (name "/BAT_ADC") (class "Default")
      (node (ref "BAT_ADC") (pin "TP") (pinfunction "TP_TP") (pintype "input"))
      (node (ref "R60") (pin "1") (pinfunction "1_1") (pintype "passive"))
      (node (ref "R61") (pin "2") (pinfunction "2_2") (pintype "passive"))
      (node (ref "U2") (pin "15") (pinfunction "PA1_15") (pintype "bidirectional"))
    )
    (net (code "8") (name "/BAT_PACK_POS") (class "Default")
      (node (ref "BAT") (pin "1") (pinfunction "1_1") (pintype "passive"))
      (node (ref "BAT_PACK_POS") (pin "TP") (pinfunction "TP_TP") (pintype "input"))
      (node (ref "C51") (pin "+") (pinfunction "+_+") (pintype "passive"))
      (node (ref "C52") (pin "+") (pinfunction "+_+") (pintype "passive"))
      (node (ref "D10") (pin "C") (pinfunction "C_C") (pintype "passive"))
      (node (ref "JP3") (pin "1") (pinfunction "1_1") (pintype "passive"))
      (node (ref "R30") (pin "1") (pinfunction "1_1") (pintype "passive"))
      (node (ref "R34") (pin "1") (pinfunction "1_1") (pintype "passive"))
      (node (ref "R51") (pin "2") (pinfunction "2_2") (pintype "passive"))
    )
    (net (code "9") (name "/BTN_1") (class "Default")
      (node (ref "BTN_1") (pin "TP") (pinfunction "TP_TP") (pintype "input"))
      (node (ref "D2") (pin "A") (pinfunction "A_A") (pintype "passive"))
      (node (ref "R6") (pin "2") (pinfunction "2_2") (pintype "passive"))
      (node (ref "R7") (pin "1") (pinfunction "1_1") (pintype "passive"))
      (node (ref "S2") (pin "P$1") (pinfunction "P_P$1") (pintype "passive"))
      (node (ref "S2") (pin "P$2") (pinfunction "P1_P$2") (pintype "passive"))
      (node (ref "U2") (pin "33") (pinfunction "PB12_33") (pintype "bidirectional"))
    )
    (net (code "10") (name "/BTN_2") (class "Default")
      (node (ref "BTN_2") (pin "TP") (pinfunction "TP_TP") (pintype "input"))
      (node (ref "D3") (pin "A") (pinfunction "A_A") (pintype "passive"))
      (node (ref "R5") (pin "2") (pinfunction "2_2") (pintype "passive"))
      (node (ref "R8") (pin "1") (pinfunction "1_1") (pintype "passive"))
      (node (ref "S3") (pin "P$1") (pinfunction "P_P$1") (pintype "passive"))
      (node (ref "S3") (pin "P$2") (pinfunction "P1_P$2") (pintype "passive"))
      (node (ref "U2") (pin "38") (pinfunction "PC7_38") (pintype "bidirectional"))
    )
    (net (code "11") (name "/BTN_3") (class "Default")
      (node (ref "BTN_3") (pin "TP") (pinfunction "TP_TP") (pintype "input"))
      (node (ref "D4") (pin "A") (pinfunction "A_A") (pintype "passive"))
      (node (ref "R12") (pin "2") (pinfunction "2_2") (pintype "passive"))
      (node (ref "R13") (pin "1") (pinfunction "1_1") (pintype "passive"))
      (node (ref "S4") (pin "P$1") (pinfunction "P_P$1") (pintype "passive"))
      (node (ref "S4") (pin "P$2") (pinfunction "P1_P$2") (pintype "passive"))
      (node (ref "U2") (pin "39") (pinfunction "PC8_39") (pintype "bidirectional"))
    )
    (net (code "12") (name "/BTN_4") (class "Default")
      (node (ref "BTN_4") (pin "TP") (pinfunction "TP_TP") (pintype "input"))
      (node (ref "D5") (pin "A") (pinfunction "A_A") (pintype "passive"))
      (node (ref "R16") (pin "2") (pinfunction "2_2") (pintype "passive"))
      (node (ref "R17") (pin "1") (pinfunction "1_1") (pintype "passive"))
      (node (ref "S5") (pin "P$1") (pinfunction "P_P$1") (pintype "passive"))
      (node (ref "S5") (pin "P$2") (pinfunction "P1_P$2") (pintype "passive"))
      (node (ref "U2") (pin "40") (pinfunction "PC9_40") (pintype "bidirectional"))
    )
    (net (code "13") (name "/BT_HCI_RXD") (class "Default")
      (node (ref "BT_RX") (pin "TP") (pinfunction "TP_TP") (pintype "input"))
      (node (ref "CONFIG_INTERFACE_TEST_POINT") (pin "3") (pinfunction "3_3") (pintype "passive"))
      (node (ref "IC2") (pin "22") (pinfunction "HCI_RXD_22") (pintype "bidirectional"))
      (node (ref "U2") (pin "42") (pinfunction "PA9_42") (pintype "bidirectional"))
    )
    (net (code "14") (name "/BT_HCI_TXD") (class "Default")
      (node (ref "BT_TX") (pin "TP") (pinfunction "TP_TP") (pintype "input"))
      (node (ref "CONFIG_INTERFACE_TEST_POINT") (pin "4") (pinfunction "4_4") (pintype "passive"))
      (node (ref "IC2") (pin "23") (pinfunction "HCI_TXD_23") (pintype "bidirectional"))
      (node (ref "U2") (pin "43") (pinfunction "PA10_43") (pintype "bidirectional"))
    )
    (net (code "15") (name "/BT_NRST") (class "Default")
      (node (ref "IC2") (pin "21") (pinfunction "RST_N_21") (pintype "bidirectional"))
      (node (ref "R3") (pin "2") (pinfunction "2_2") (pintype "passive"))
      (node (ref "U1") (pin "1") (pinfunction "VOUT_1") (pintype "passive"))
    )
    (net (code "16") (name "/BT_P2_0_MODE") (class "Default")
      (node (ref "CONFIG_INTERFACE_TEST_POINT") (pin "1") (pinfunction "1_1") (pintype "passive"))
      (node (ref "IC2") (pin "18") (pinfunction "P2_0/MODE_18") (pintype "bidirectional"))
    )
    (net (code "17") (name "/CHARGER_CH_PRECH") (class "Default")
      (node (ref "Q7") (pin "1") (pinfunction "G_1") (pintype "passive"))
      (node (ref "U2") (pin "54") (pinfunction "PD2_54") (pintype "bidirectional"))
    )
    (net (code "18") (name "/CHARGER_SS") (class "Default")
      (node (ref "U$3") (pin "6") (pinfunction "S/S_6") (pintype "bidirectional"))
      (node (ref "U2") (pin "53") (pinfunction "PC12_53") (pintype "bidirectional"))
    )
    (net (code "19") (name "/GPS_EXTINT") (class "Default")
      (node (ref "GPS>") (pin "5") (pinfunction "5_5") (pintype "passive"))
      (node (ref "U2") (pin "36") (pinfunction "PB15_36") (pintype "bidirectional"))
    )
    (net (code "20") (name "/GPS_NRESET") (class "Default")
      (node (ref "GPS>") (pin "6") (pinfunction "6_6") (pintype "passive"))
      (node (ref "U2") (pin "37") (pinfunction "PC6_37") (pintype "bidirectional"))
    )
    (net (code "21") (name "/GPS_RXD") (class "Default")
      (node (ref "GPS>") (pin "7") (pinfunction "7_7") (pintype "passive"))
      (node (ref "U2") (pin "51") (pinfunction "PC10_51") (pintype "bidirectional"))
    )
    (net (code "22") (name "/GPS_SCL") (class "Default")
      (node (ref "GPS>") (pin "3") (pinfunction "3_3") (pintype "passive"))
      (node (ref "U2") (pin "34") (pinfunction "PB13_34") (pintype "bidirectional"))
    )
    (net (code "23") (name "/GPS_SDA") (class "Default")
      (node (ref "GPS>") (pin "4") (pinfunction "4_4") (pintype "passive"))
      (node (ref "U2") (pin "35") (pinfunction "PB14_35") (pintype "bidirectional"))
    )
    (net (code "24") (name "/GPS_TXD") (class "Default")
      (node (ref "GPS>") (pin "8") (pinfunction "8_8") (pintype "passive"))
      (node (ref "U2") (pin "52") (pinfunction "PC11_52") (pintype "bidirectional"))
    )
    (net (code "25") (name "/IND_LED_B") (class "Default")
      (node (ref "R11") (pin "2") (pinfunction "2_2") (pintype "passive"))
      (node (ref "U2") (pin "26") (pinfunction "PB0_26") (pintype "bidirectional"))
    )
    (net (code "26") (name "/IND_LED_G") (class "Default")
      (node (ref "R10") (pin "2") (pinfunction "2_2") (pintype "passive"))
      (node (ref "U2") (pin "25") (pinfunction "PC5_25") (pintype "bidirectional"))
    )
    (net (code "27") (name "/IND_LED_R") (class "Default")
      (node (ref "R15") (pin "2") (pinfunction "2_2") (pintype "passive"))
      (node (ref "U2") (pin "28") (pinfunction "PB2_28") (pintype "bidirectional"))
    )
    (net (code "28") (name "/IND_LED_W") (class "Default")
      (node (ref "R14") (pin "2") (pinfunction "2_2") (pintype "passive"))
      (node (ref "U2") (pin "27") (pinfunction "PB1_27") (pintype "bidirectional"))
    )
    (net (code "29") (name "/INT_POWER") (class "Default")
      (node (ref "C21") (pin "2") (pinfunction "2_2") (pintype "passive"))
      (node (ref "C22") (pin "2") (pinfunction "2_2") (pintype "passive"))
      (node (ref "C23") (pin "2") (pinfunction "2_2") (pintype "passive"))
      (node (ref "C25") (pin "2") (pinfunction "2_2") (pintype "passive"))
      (node (ref "C26") (pin "2") (pinfunction "2_2") (pintype "passive"))
      (node (ref "C27") (pin "2") (pinfunction "2_2") (pintype "passive"))
      (node (ref "C29") (pin "2") (pinfunction "2_2") (pintype "passive"))
      (node (ref "C30") (pin "1") (pinfunction "1_1") (pintype "passive"))
      (node (ref "L2") (pin "1") (pinfunction "1_1") (pintype "passive"))
      (node (ref "L3") (pin "2") (pinfunction "2_2") (pintype "passive"))
      (node (ref "U$1") (pin "1") (pinfunction "VDD1_1") (pintype "power_in"))
      (node (ref "U$1") (pin "17") (pinfunction "VREG_17") (pintype "power_in"))
      (node (ref "U$1") (pin "4") (pinfunction "VDD2_4") (pintype "power_in"))
    )
    (net (code "30") (name "/MCU_WAKEUP") (class "Default")
      (node (ref "D2") (pin "C") (pinfunction "C_C") (pintype "passive"))
      (node (ref "D3") (pin "C") (pinfunction "C_C") (pintype "passive"))
      (node (ref "D4") (pin "C") (pinfunction "C_C") (pintype "passive"))
      (node (ref "D5") (pin "C") (pinfunction "C_C") (pintype "passive"))
      (node (ref "D8") (pin "C") (pinfunction "C_C") (pintype "passive"))
      (node (ref "D9") (pin "C") (pinfunction "C_C") (pintype "passive"))
      (node (ref "U2") (pin "14") (pinfunction "PA0_14") (pintype "bidirectional"))
    )
    (net (code "31") (name "/N$14") (class "Default")
      (node (ref "U2") (pin "41") (pinfunction "PA8_41") (pintype "bidirectional"))
    )
    (net (code "32") (name "/N$78") (class "Default")
      (node (ref "B4") (pin "2") (pinfunction "2_2") (pintype "passive"))
      (node (ref "CONFIG_INTERFACE_TEST_POINT") (pin "2") (pinfunction "2_2") (pintype "passive"))
    )
    (net (code "33") (name "/NRST") (class "Default")
      (node (ref "BTN_NRST") (pin "TP") (pinfunction "TP_TP") (pintype "input"))
      (node (ref "NRST_MCU") (pin "TP") (pinfunction "TP_TP") (pintype "input"))
      (node (ref "PR0>") (pin "5") (pinfunction "5_5") (pintype "passive"))
      (node (ref "R4") (pin "2") (pinfunction "2_2") (pintype "passive"))
      (node (ref "R59") (pin "2") (pinfunction "2_2") (pintype "passive"))
      (node (ref "S1") (pin "P$3") (pinfunction "S_P$3") (pintype "passive"))
      (node (ref "S1") (pin "P$4") (pinfunction "S1_P$4") (pintype "passive"))
      (node (ref "U2") (pin "7") (pinfunction "NRST_7") (pintype "bidirectional"))
    )
    (net (code "34") (name "/POW_LED_G1") (class "Default")
      (node (ref "R20") (pin "1") (pinfunction "1_1") (pintype "passive"))
      (node (ref "U2") (pin "22") (pinfunction "PA6_22") (pintype "bidirectional"))
    )
    (net (code "35") (name "/POW_LED_G2") (class "Default")
      (node (ref "R19") (pin "1") (pinfunction "1_1") (pintype "passive"))
      (node (ref "U2") (pin "21") (pinfunction "PA5_21") (pintype "bidirectional"))
    )
    (net (code "36") (name "/POW_LED_G3") (class "Default")
      (node (ref "R18") (pin "1") (pinfunction "1_1") (pintype "passive"))
      (node (ref "U2") (pin "20") (pinfunction "PA4_20") (pintype "bidirectional"))
    )
    (net (code "37") (name "/POW_LED_R") (class "Default")
      (node (ref "R21") (pin "1") (pinfunction "1_1") (pintype "passive"))
      (node (ref "U2") (pin "24") (pinfunction "PC4_24") (pintype "bidirectional"))
    )
    (net (code "38") (name "/POW_LED_Y") (class "Default")
      (node (ref "R22") (pin "1") (pinfunction "1_1") (pintype "passive"))
      (node (ref "U2") (pin "23") (pinfunction "PA7_23") (pintype "bidirectional"))
    )
    (net (code "39") (name "/RESERVED") (class "Default")
      (node (ref "U2") (pin "30") (pinfunction "PB11_30") (pintype "bidirectional"))
    )
    (net (code "40") (name "/RF_SIGNAL") (class "Default")
      (node (ref "C37") (pin "2") (pinfunction "2_2") (pintype "passive"))
      (node (ref "L7") (pin "2") (pinfunction "2_2") (pintype "passive"))
      (node (ref "RF_SIGNAL") (pin "TP") (pinfunction "TP_TP") (pintype "input"))
      (node (ref "U$2") (pin "1") (pinfunction "RF_IN_1") (pintype "bidirectional"))
    )
    (net (code "41") (name "/RF_SIGNAL_AMPLIFIED") (class "Default")
      (node (ref "J3") (pin "S") (pinfunction "OUT_S") (pintype "bidirectional"))
      (node (ref "U$2") (pin "4") (pinfunction "RF_OUT_4") (pintype "bidirectional"))
    )
    (net (code "42") (name "/SPI2_CLK") (class "Default")
      (node (ref "SPI2_CLK") (pin "TP") (pinfunction "TP_TP") (pintype "input"))
      (node (ref "U$1") (pin "9") (pinfunction "CLK_9") (pintype "input"))
      (node (ref "U2") (pin "29") (pinfunction "PB10_29") (pintype "bidirectional"))
    )
    (net (code "43") (name "/SPI2_IRQ") (class "Default")
      (node (ref "SPI2_IRQ") (pin "TP") (pinfunction "TP_TP") (pintype "input"))
      (node (ref "U$1") (pin "14") (pinfunction "IRQ_14") (pintype "output"))
      (node (ref "U2") (pin "8") (pinfunction "PC0_8") (pintype "bidirectional"))
    )
    (net (code "44") (name "/SPI2_MISO") (class "Default")
      (node (ref "SPI2_MISO") (pin "TP") (pinfunction "TP_TP") (pintype "input"))
      (node (ref "U$1") (pin "10") (pinfunction "MISO_SDO_10") (pintype "output"))
      (node (ref "U2") (pin "10") (pinfunction "PC2_10") (pintype "bidirectional"))
    )
    (net (code "45") (name "/SPI2_MOSI") (class "Default")
      (node (ref "SPI2_MOSI") (pin "TP") (pinfunction "TP_TP") (pintype "input"))
      (node (ref "U$1") (pin "12") (pinfunction "MOSI_SDI_12") (pintype "input"))
      (node (ref "U2") (pin "11") (pinfunction "PC3_11") (pintype "bidirectional"))
    )
    (net (code "46") (name "/SPI2_SEL_RFTX") (class "Default")
      (node (ref "SPI2_SEL_RFTX") (pin "TP") (pinfunction "TP_TP") (pintype "input"))
      (node (ref "U$1") (pin "8") (pinfunction "SEL_8") (pintype "input"))
      (node (ref "U2") (pin "9") (pinfunction "PC1_9") (pintype "bidirectional"))
    )
    (net (code "47") (name "/SWDCLK") (class "Default")
      (node (ref "PR0>") (pin "3") (pinfunction "3_3") (pintype "passive"))
      (node (ref "U2") (pin "49") (pinfunction "PA14_49") (pintype "bidirectional"))
    )
    (net (code "48") (name "/SWDIO") (class "Default")
      (node (ref "PR0>") (pin "2") (pinfunction "2_2") (pintype "passive"))
      (node (ref "U2") (pin "46") (pinfunction "PA13_46") (pintype "bidirectional"))
    )
    (net (code "49") (name "/SWD_RX") (class "Default")
      (node (ref "U3") (pin "12") (pinfunction "RX_12") (pintype "input"))
    )
    (net (code "50") (name "/SWD_RXD") (class "Default")
      (node (ref "SWD_RXD") (pin "TP") (pinfunction "TP_TP") (pintype "input"))
      (node (ref "U2") (pin "16") (pinfunction "PA2_16") (pintype "bidirectional"))
    )
    (net (code "51") (name "/SWD_TX") (class "Default")
      (node (ref "U3") (pin "10") (pinfunction "TX_10") (pintype "output"))
    )
    (net (code "52") (name "/SWD_TXD") (class "Default")
      (node (ref "SWD_TXD") (pin "TP") (pinfunction "TP_TP") (pintype "input"))
      (node (ref "U2") (pin "17") (pinfunction "PA3_17") (pintype "bidirectional"))
    )
    (net (code "53") (name "/USB_DATA_N") (class "Default")
      (node (ref "J2") (pin "D-") (pinfunction "D-_D-") (pintype "bidirectional"))
      (node (ref "U2") (pin "44") (pinfunction "PA11_44") (pintype "bidirectional"))
      (node (ref "U4") (pin "1") (pinfunction "IO1_1") (pintype "bidirectional"))
    )
    (net (code "54") (name "/USB_DATA_P") (class "Default")
      (node (ref "J2") (pin "D+") (pinfunction "D+_D+") (pintype "bidirectional"))
      (node (ref "R27") (pin "2") (pinfunction "2_2") (pintype "passive"))
      (node (ref "U2") (pin "45") (pinfunction "PA12_45") (pintype "bidirectional"))
      (node (ref "U4") (pin "2") (pinfunction "IO2_2") (pintype "bidirectional"))
    )
    (net (code "55") (name "/V+STM") (class "Default")
      (node (ref "B1") (pin "2") (pinfunction "2_2") (pintype "passive"))
      (node (ref "C10") (pin "2") (pinfunction "2_2") (pintype "passive"))
      (node (ref "C16") (pin "2") (pinfunction "2_2") (pintype "passive"))
      (node (ref "C4") (pin "1") (pinfunction "1_1") (pintype "passive"))
      (node (ref "C5") (pin "2") (pinfunction "2_2") (pintype "passive"))
      (node (ref "C6") (pin "2") (pinfunction "2_2") (pintype "passive"))
      (node (ref "C8") (pin "1") (pinfunction "1_1") (pintype "passive"))
      (node (ref "C9") (pin "1") (pinfunction "1_1") (pintype "passive"))
      (node (ref "U2") (pin "1") (pinfunction "VLCD_1") (pintype "power_in"))
      (node (ref "U2") (pin "13") (pinfunction "VDDA_13") (pintype "power_in"))
      (node (ref "U2") (pin "19") (pinfunction "VDD_2_19") (pintype "power_in"))
      (node (ref "U2") (pin "32") (pinfunction "VDD_3_32") (pintype "power_in"))
      (node (ref "U2") (pin "64") (pinfunction "VDD_64") (pintype "power_in"))
    )
    (net (code "56") (name "/VIBRATOR") (class "Default")
      (node (ref "Q3") (pin "1") (pinfunction "G_1") (pintype "passive"))
      (node (ref "R25") (pin "1") (pinfunction "1_1") (pintype "passive"))
      (node (ref "U2") (pin "50") (pinfunction "PA15_50") (pintype "bidirectional"))
    )
    (net (code "57") (name "GND") (class "Default")
      (node (ref "C10") (pin "1") (pinfunction "1_1") (pintype "passive"))
      (node (ref "C11") (pin "1") (pinfunction "1_1") (pintype "passive"))
      (node (ref "C12") (pin "1") (pinfunction "1_1") (pintype "passive"))
      (node (ref "C13") (pin "1") (pinfunction "1_1") (pintype "passive"))
      (node (ref "C14") (pin "2") (pinfunction "2_2") (pintype "passive"))
      (node (ref "C15") (pin "2") (pinfunction "2_2") (pintype "passive"))
      (node (ref "C16") (pin "1") (pinfunction "1_1") (pintype "passive"))
      (node (ref "C17") (pin "1") (pinfunction "1_1") (pintype "passive"))
      (node (ref "C18") (pin "1") (pinfunction "1_1") (pintype "passive"))
      (node (ref "C19") (pin "2") (pinfunction "22_2") (pintype "passive"))
      (node (ref "C20") (pin "2") (pinfunction "2_2") (pintype "passive"))
      (node (ref "C21") (pin "1") (pinfunction "1_1") (pintype "passive"))
      (node (ref "C22") (pin "1") (pinfunction "1_1") (pintype "passive"))
      (node (ref "C23") (pin "1") (pinfunction "1_1") (pintype "passive"))
      (node (ref "C24") (pin "1") (pinfunction "1_1") (pintype "passive"))
      (node (ref "C25") (pin "1") (pinfunction "1_1") (pintype "passive"))
      (node (ref "C26") (pin "1") (pinfunction "1_1") (pintype "passive"))
      (node (ref "C27") (pin "1") (pinfunction "1_1") (pintype "passive"))
      (node (ref "C32") (pin "1") (pinfunction "1_1") (pintype "passive"))
      (node (ref "C33") (pin "2") (pinfunction "2_2") (pintype "passive"))
      (node (ref "C34") (pin "1") (pinfunction "1_1") (pintype "passive"))
      (node (ref "C36") (pin "1") (pinfunction "1_1") (pintype "passive"))
      (node (ref "C37") (pin "1") (pinfunction "1_1") (pintype "passive"))
      (node (ref "C4") (pin "2") (pinfunction "2_2") (pintype "passive"))
      (node (ref "C47") (pin "1") (pinfunction "1_1") (pintype "passive"))
      (node (ref "C48") (pin "-") (pinfunction "-_-") (pintype "passive"))
      (node (ref "C49") (pin "1") (pinfunction "1_1") (pintype "passive"))
      (node (ref "C5") (pin "1") (pinfunction "1_1") (pintype "passive"))
      (node (ref "C51") (pin "-") (pinfunction "-_-") (pintype "passive"))
      (node (ref "C52") (pin "-") (pinfunction "-_-") (pintype "passive"))
      (node (ref "C53") (pin "-") (pinfunction "-_-") (pintype "passive"))
      (node (ref "C54") (pin "-") (pinfunction "-_-") (pintype "passive"))
      (node (ref "C55") (pin "-") (pinfunction "-_-") (pintype "passive"))
      (node (ref "C56") (pin "-") (pinfunction "-_-") (pintype "passive"))
      (node (ref "C57") (pin "-") (pinfunction "-_-") (pintype "passive"))
      (node (ref "C58") (pin "-") (pinfunction "-_-") (pintype "passive"))
      (node (ref "C59") (pin "-") (pinfunction "-_-") (pintype "passive"))
      (node (ref "C6") (pin "1") (pinfunction "1_1") (pintype "passive"))
      (node (ref "C60") (pin "-") (pinfunction "-_-") (pintype "passive"))
      (node (ref "C61") (pin "-") (pinfunction "-_-") (pintype "passive"))
      (node (ref "C7") (pin "2") (pinfunction "2_2") (pintype "passive"))
      (node (ref "C8") (pin "2") (pinfunction "2_2") (pintype "passive"))
      (node (ref "C9") (pin "2") (pinfunction "2_2") (pintype "passive"))
      (node (ref "CONFIG_INTERFACE_TEST_POINT") (pin "5") (pinfunction "5_5") (pintype "passive"))
      (node (ref "D6") (pin "A") (pinfunction "A_A") (pintype "passive"))
      (node (ref "FB3") (pin "1") (pinfunction "1_1") (pintype "passive"))
      (node (ref "FB4") (pin "1") (pinfunction "1_1") (pintype "passive"))
      (node (ref "GPS>") (pin "2") (pinfunction "2_2") (pintype "passive"))
      (node (ref "IC2") (pin "1") (pinfunction "GND(1)_1") (pintype "bidirectional"))
      (node (ref "IC2") (pin "2") (pinfunction "GND(2)_2") (pintype "bidirectional"))
      (node (ref "IC2") (pin "3") (pinfunction "GND(3)_3") (pintype "bidirectional"))
      (node (ref "IC2") (pin "31") (pinfunction "GND(4)_31") (pintype "bidirectional"))
      (node (ref "IC2") (pin "32") (pinfunction "GND(5)_32") (pintype "bidirectional"))
      (node (ref "IC2") (pin "33") (pinfunction "GND(6)_33") (pintype "bidirectional"))
      (node (ref "J1") (pin "GND") (pinfunction "GND_GND") (pintype "power_in"))
      (node (ref "J1") (pin "SHIELD1") (pinfunction "SHIELD_SHIELD1") (pintype "bidirectional"))
      (node (ref "J1") (pin "SHIELD2") (pinfunction "SHIELD_SHIELD2") (pintype "bidirectional"))
      (node (ref "J1") (pin "SHIELD3") (pinfunction "SHIELD_SHIELD3") (pintype "bidirectional"))
      (node (ref "J3") (pin "GND") (pinfunction "GND_GND") (pintype "bidirectional"))
      (node (ref "J4") (pin "GND") (pinfunction "GND_GND") (pintype "power_in"))
      (node (ref "J4") (pin "SHIELD1") (pinfunction "SHIELD_SHIELD1") (pintype "bidirectional"))
      (node (ref "J4") (pin "SHIELD2") (pinfunction "SHIELD_SHIELD2") (pintype "bidirectional"))
      (node (ref "J4") (pin "SHIELD3") (pinfunction "SHIELD_SHIELD3") (pintype "bidirectional"))
      (node (ref "L5") (pin "1") (pinfunction "1_1") (pintype "passive"))
      (node (ref "LED10") (pin "C") (pinfunction "C_C") (pintype "passive"))
      (node (ref "LED2") (pin "C") (pinfunction "C_C") (pintype "passive"))
      (node (ref "LED3") (pin "C") (pinfunction "C_C") (pintype "passive"))
      (node (ref "LED4") (pin "C") (pinfunction "C_C") (pintype "passive"))
      (node (ref "LED5") (pin "C") (pinfunction "C_C") (pintype "passive"))
      (node (ref "LED6") (pin "C") (pinfunction "C_C") (pintype "passive"))
      (node (ref "LED7") (pin "C") (pinfunction "C_C") (pintype "passive"))
      (node (ref "LED8") (pin "C") (pinfunction "C_C") (pintype "passive"))
      (node (ref "LED9") (pin "C") (pinfunction "C_C") (pintype "passive"))
      (node (ref "PR0>") (pin "1") (pinfunction "1_1") (pintype "passive"))
      (node (ref "Q3") (pin "2") (pinfunction "S_2") (pintype "passive"))
      (node (ref "Q6") (pin "1") (pinfunction "1_1") (pintype "passive"))
      (node (ref "Q6") (pin "2") (pinfunction "2_2") (pintype "passive"))
      (node (ref "Q6") (pin "3") (pinfunction "3_3") (pintype "passive"))
      (node (ref "Q7") (pin "2") (pinfunction "S_2") (pintype "passive"))
      (node (ref "R13") (pin "2") (pinfunction "2_2") (pintype "passive"))
      (node (ref "R17") (pin "2") (pinfunction "2_2") (pintype "passive"))
      (node (ref "R25") (pin "2") (pinfunction "2_2") (pintype "passive"))
      (node (ref "R26") (pin "2") (pinfunction "2_2") (pintype "passive"))
      (node (ref "R28") (pin "2") (pinfunction "2_2") (pintype "passive"))
      (node (ref "R41") (pin "1") (pinfunction "1_1") (pintype "passive"))
      (node (ref "R44") (pin "2") (pinfunction "2_2") (pintype "passive"))
      (node (ref "R50") (pin "1") (pinfunction "1_1") (pintype "passive"))
      (node (ref "R52") (pin "1") (pinfunction "1_1") (pintype "passive"))
      (node (ref "R54") (pin "2") (pinfunction "2_2") (pintype "passive"))
      (node (ref "R56") (pin "2") (pinfunction "2_2") (pintype "passive"))
      (node (ref "R58") (pin "2") (pinfunction "2_2") (pintype "passive"))
      (node (ref "R61") (pin "1") (pinfunction "1_1") (pintype "passive"))
      (node (ref "R7") (pin "2") (pinfunction "2_2") (pintype "passive"))
      (node (ref "R8") (pin "2") (pinfunction "2_2") (pintype "passive"))
      (node (ref "S1") (pin "P$1") (pinfunction "P_P$1") (pintype "passive"))
      (node (ref "S1") (pin "P$2") (pinfunction "P1_P$2") (pintype "passive"))
      (node (ref "U$1") (pin "PAD") (pinfunction "GND_PAD_PAD") (pintype "power_in"))
      (node (ref "U$2") (pin "5_L") (pinfunction "RF_GND_L_5_L") (pintype "bidirectional"))
      (node (ref "U$2") (pin "5_R") (pinfunction "RF_GND_R_5_R") (pintype "bidirectional"))
      (node (ref "U$3") (pin "4") (pinfunction "GND_4") (pintype "bidirectional"))
      (node (ref "U1") (pin "2") (pinfunction "VDD_2") (pintype "passive"))
      (node (ref "U2") (pin "12") (pinfunction "VSSA_12") (pintype "power_in"))
      (node (ref "U2") (pin "18") (pinfunction "VSS_2_18") (pintype "power_in"))
      (node (ref "U2") (pin "31") (pinfunction "VSS_3_31") (pintype "power_in"))
      (node (ref "U2") (pin "47") (pinfunction "VSS_4_47") (pintype "power_in"))
      (node (ref "U2") (pin "60") (pinfunction "BOOT0_60") (pintype "input"))
      (node (ref "U2") (pin "63") (pinfunction "VSS_63") (pintype "power_in"))
      (node (ref "U3") (pin "20") (pinfunction "VSS_20") (pintype "power_in"))
      (node (ref "U4") (pin "3") (pinfunction "GND_3") (pintype "passive"))
    )
    (net (code "58") (name "Net-(B5-Pad2)") (class "Default")
      (node (ref "B5") (pin "2") (pinfunction "2_2") (pintype "passive"))
      (node (ref "D1") (pin "C") (pinfunction "C_C") (pintype "passive"))
      (node (ref "JP2") (pin "1") (pinfunction "1_1") (pintype "passive"))
    )
    (net (code "59") (name "Net-(BAT-Pad2)") (class "Default")
      (node (ref "BAT") (pin "2") (pinfunction "2_2") (pintype "passive"))
      (node (ref "R31") (pin "1") (pinfunction "1_1") (pintype "passive"))
    )
    (net (code "60") (name "Net-(BAT-Pad3)") (class "Default")
      (node (ref "BAT") (pin "3") (pinfunction "3_3") (pintype "passive"))
      (node (ref "R32") (pin "1") (pinfunction "1_1") (pintype "passive"))
    )
    (net (code "61") (name "Net-(BAT-Pad4)") (class "Default")
      (node (ref "BAT") (pin "4") (pinfunction "4_4") (pintype "passive"))
      (node (ref "R33") (pin "1") (pinfunction "1_1") (pintype "passive"))
    )
    (net (code "62") (name "Net-(C11-Pad2)") (class "Default")
      (node (ref "C11") (pin "2") (pinfunction "2_2") (pintype "passive"))
      (node (ref "R59") (pin "1") (pinfunction "1_1") (pintype "passive"))
    )
    (net (code "63") (name "Net-(C12-Pad2)") (class "Default")
      (node (ref "C12") (pin "2") (pinfunction "2_2") (pintype "passive"))
      (node (ref "R6") (pin "1") (pinfunction "1_1") (pintype "passive"))
    )
    (net (code "64") (name "Net-(C13-Pad2)") (class "Default")
      (node (ref "C13") (pin "2") (pinfunction "2_2") (pintype "passive"))
      (node (ref "R5") (pin "1") (pinfunction "1_1") (pintype "passive"))
    )
    (net (code "65") (name "Net-(C15-Pad1)") (class "Default")
      (node (ref "C15") (pin "1") (pinfunction "1_1") (pintype "passive"))
      (node (ref "Q1") (pin "1") (pinfunction "1_1") (pintype "passive"))
      (node (ref "R9") (pin "1") (pinfunction "1_1") (pintype "passive"))
    )
    (net (code "66") (name "Net-(C17-Pad2)") (class "Default")
      (node (ref "C17") (pin "2") (pinfunction "2_2") (pintype "passive"))
      (node (ref "R12") (pin "1") (pinfunction "1_1") (pintype "passive"))
    )
    (net (code "67") (name "Net-(C18-Pad2)") (class "Default")
      (node (ref "C18") (pin "2") (pinfunction "2_2") (pintype "passive"))
      (node (ref "R16") (pin "1") (pinfunction "1_1") (pintype "passive"))
    )
    (net (code "68") (name "Net-(C19-11)") (class "Default")
      (node (ref "C19") (pin "1") (pinfunction "11_1") (pintype "passive"))
      (node (ref "U3") (pin "2") (pinfunction "OSC1_2") (pintype "input"))
    )
    (net (code "69") (name "Net-(C19-33)") (class "Default")
      (node (ref "C19") (pin "3") (pinfunction "33_3") (pintype "passive"))
      (node (ref "U3") (pin "3") (pinfunction "OSC2_3") (pintype "output"))
    )
    (net (code "70") (name "Net-(C28-Pad1)") (class "Default")
      (node (ref "C28") (pin "1") (pinfunction "1_1") (pintype "passive"))
      (node (ref "L4") (pin "1") (pinfunction "1_1") (pintype "passive"))
    )
    (net (code "71") (name "Net-(C28-Pad2)") (class "Default")
      (node (ref "C28") (pin "2") (pinfunction "2_2") (pintype "passive"))
      (node (ref "C33") (pin "1") (pinfunction "1_1") (pintype "passive"))
      (node (ref "C35") (pin "2") (pinfunction "2_2") (pintype "passive"))
      (node (ref "L5") (pin "2") (pinfunction "2_2") (pintype "passive"))
    )
    (net (code "72") (name "Net-(C31-Pad1)") (class "Default")
      (node (ref "C31") (pin "1") (pinfunction "1_1") (pintype "passive"))
      (node (ref "L1") (pin "1") (pinfunction "1_1") (pintype "passive"))
    )
    (net (code "73") (name "Net-(C31-Pad2)") (class "Default")
      (node (ref "C31") (pin "2") (pinfunction "2_2") (pintype "passive"))
      (node (ref "C32") (pin "2") (pinfunction "2_2") (pintype "passive"))
      (node (ref "C34") (pin "2") (pinfunction "2_2") (pintype "passive"))
      (node (ref "L6") (pin "1") (pinfunction "1_1") (pintype "passive"))
    )
    (net (code "74") (name "Net-(C35-Pad1)") (class "Default")
      (node (ref "C35") (pin "1") (pinfunction "1_1") (pintype "passive"))
      (node (ref "C36") (pin "2") (pinfunction "2_2") (pintype "passive"))
      (node (ref "L6") (pin "2") (pinfunction "2_2") (pintype "passive"))
      (node (ref "L7") (pin "1") (pinfunction "1_1") (pintype "passive"))
    )
    (net (code "75") (name "Net-(C47-Pad2)") (class "Default")
      (node (ref "C47") (pin "2") (pinfunction "2_2") (pintype "passive"))
      (node (ref "R45") (pin "2") (pinfunction "2_2") (pintype "passive"))
    )
    (net (code "76") (name "Net-(C63-Pad-)") (class "Default")
      (node (ref "C63") (pin "-") (pinfunction "-_-") (pintype "passive"))
      (node (ref "D10") (pin "A") (pinfunction "A_A") (pintype "passive"))
      (node (ref "L8") (pin "3") (pinfunction "3_3") (pintype "passive"))
    )
    (net (code "77") (name "Net-(D6-PadC)") (class "Default")
      (node (ref "D6") (pin "C") (pinfunction "C_C") (pintype "passive"))
      (node (ref "D7") (pin "C") (pinfunction "C_C") (pintype "passive"))
      (node (ref "Q6") (pin "4") (pinfunction "4_4") (pintype "passive"))
      (node (ref "R41") (pin "2") (pinfunction "2_2") (pintype "passive"))
      (node (ref "R42") (pin "1") (pinfunction "1_1") (pintype "passive"))
    )
    (net (code "78") (name "Net-(D7-PadA)") (class "Default")
      (node (ref "D7") (pin "A") (pinfunction "A_A") (pintype "passive"))
      (node (ref "R42") (pin "2") (pinfunction "2_2") (pintype "passive"))
      (node (ref "R43") (pin "2") (pinfunction "2_2") (pintype "passive"))
    )
    (net (code "79") (name "Net-(FB1-Pad1)") (class "Default")
      (node (ref "FB1") (pin "1") (pinfunction "1_1") (pintype "passive"))
      (node (ref "J2") (pin "VBUS") (pinfunction "VBUS_VBUS") (pintype "power_in"))
    )
    (net (code "80") (name "Net-(FB3-Pad2)") (class "Default")
      (node (ref "FB3") (pin "2") (pinfunction "2_2") (pintype "passive"))
      (node (ref "J2") (pin "GND") (pinfunction "GND_GND") (pintype "power_in"))
    )
    (net (code "81") (name "Net-(FB4-Pad2)") (class "Default")
      (node (ref "FB4") (pin "2") (pinfunction "2_2") (pintype "passive"))
      (node (ref "J2") (pin "SHIELD1") (pinfunction "SHIELD_SHIELD1") (pintype "bidirectional"))
      (node (ref "J2") (pin "SHIELD2") (pinfunction "SHIELD_SHIELD2") (pintype "bidirectional"))
      (node (ref "J2") (pin "SHIELD3") (pinfunction "SHIELD_SHIELD3") (pintype "bidirectional"))
    )
    (net (code "82") (name "Net-(IC2-P0_2{slash}LED)") (class "Default")
      (node (ref "IC2") (pin "30") (pinfunction "P0_2/LED_30") (pintype "bidirectional"))
      (node (ref "LED1") (pin "C") (pinfunction "C_C") (pintype "passive"))
    )
    (net (code "83") (name "Net-(IC2-VBAT)") (class "Default")
      (node (ref "B3") (pin "2") (pinfunction "2_2") (pintype "passive"))
      (node (ref "IC2") (pin "4") (pinfunction "VBAT_4") (pintype "bidirectional"))
      (node (ref "LED1") (pin "A") (pinfunction "A_A") (pintype "passive"))
      (node (ref "R3") (pin "1") (pinfunction "1_1") (pintype "passive"))
      (node (ref "U1") (pin "3") (pinfunction "VSS_3") (pintype "passive"))
    )
    (net (code "84") (name "Net-(IC3-ADJ)") (class "Default")
      (node (ref "C55") (pin "+") (pinfunction "+_+") (pintype "passive"))
      (node (ref "IC3") (pin "1") (pinfunction "ADJ_1") (pintype "input"))
      (node (ref "R53") (pin "2") (pinfunction "2_2") (pintype "passive"))
      (node (ref "R54") (pin "1") (pinfunction "1_1") (pintype "passive"))
    )
    (net (code "85") (name "Net-(IC3-IN)") (class "Default")
      (node (ref "C53") (pin "+") (pinfunction "+_+") (pintype "passive"))
      (node (ref "C56") (pin "+") (pinfunction "+_+") (pintype "passive"))
      (node (ref "IC3") (pin "2") (pinfunction "IN_2") (pintype "input"))
      (node (ref "IC5") (pin "2") (pinfunction "IN_2") (pintype "input"))
      (node (ref "JP3") (pin "2") (pinfunction "2_2") (pintype "passive"))
      (node (ref "R60") (pin "2") (pinfunction "2_2") (pintype "passive"))
    )
    (net (code "86") (name "Net-(IC5-ADJ)") (class "Default")
      (node (ref "C58") (pin "+") (pinfunction "+_+") (pintype "passive"))
      (node (ref "IC5") (pin "1") (pinfunction "ADJ_1") (pintype "input"))
      (node (ref "R55") (pin "2") (pinfunction "2_2") (pintype "passive"))
      (node (ref "R56") (pin "1") (pinfunction "1_1") (pintype "passive"))
    )
    (net (code "87") (name "Net-(IC6-ADJ)") (class "Default")
      (node (ref "C61") (pin "+") (pinfunction "+_+") (pintype "passive"))
      (node (ref "IC6") (pin "1") (pinfunction "ADJ_1") (pintype "input"))
      (node (ref "R57") (pin "2") (pinfunction "2_2") (pintype "passive"))
      (node (ref "R58") (pin "1") (pinfunction "1_1") (pintype "passive"))
    )
    (net (code "88") (name "Net-(J4-PadD+)") (class "Default")
      (node (ref "J4") (pin "D+") (pinfunction "D+_D+") (pintype "bidirectional"))
      (node (ref "USB_DP") (pin "TP") (pinfunction "TP_TP") (pintype "input"))
    )
    (net (code "89") (name "Net-(J4-PadD-)") (class "Default")
      (node (ref "J4") (pin "D-") (pinfunction "D-_D-") (pintype "bidirectional"))
      (node (ref "USB_DN") (pin "TP") (pinfunction "TP_TP") (pintype "input"))
    )
    (net (code "90") (name "Net-(J4-PadID)") (class "Default")
      (node (ref "J4") (pin "ID") (pinfunction "ID_ID") (pintype "bidirectional"))
      (node (ref "USB_ID") (pin "TP") (pinfunction "TP_TP") (pintype "input"))
    )
    (net (code "91") (name "Net-(L8-Pad4)") (class "Default")
      (node (ref "L8") (pin "4") (pinfunction "4_4") (pintype "passive"))
      (node (ref "R49") (pin "2") (pinfunction "2_2") (pintype "passive"))
      (node (ref "R50") (pin "2") (pinfunction "2_2") (pintype "passive"))
    )
    (net (code "92") (name "Net-(LED2-PadA)") (class "Default")
      (node (ref "LED2") (pin "A") (pinfunction "A_A") (pintype "passive"))
      (node (ref "R10") (pin "1") (pinfunction "1_1") (pintype "passive"))
    )
    (net (code "93") (name "Net-(LED3-PadA)") (class "Default")
      (node (ref "LED3") (pin "A") (pinfunction "A_A") (pintype "passive"))
      (node (ref "R11") (pin "1") (pinfunction "1_1") (pintype "passive"))
    )
    (net (code "94") (name "Net-(LED4-PadA)") (class "Default")
      (node (ref "LED4") (pin "A") (pinfunction "A_A") (pintype "passive"))
      (node (ref "R14") (pin "1") (pinfunction "1_1") (pintype "passive"))
    )
    (net (code "95") (name "Net-(LED5-PadA)") (class "Default")
      (node (ref "LED5") (pin "A") (pinfunction "A_A") (pintype "passive"))
      (node (ref "R15") (pin "1") (pinfunction "1_1") (pintype "passive"))
    )
    (net (code "96") (name "Net-(LED6-PadA)") (class "Default")
      (node (ref "LED6") (pin "A") (pinfunction "A_A") (pintype "passive"))
      (node (ref "R18") (pin "2") (pinfunction "2_2") (pintype "passive"))
    )
    (net (code "97") (name "Net-(LED7-PadA)") (class "Default")
      (node (ref "LED7") (pin "A") (pinfunction "A_A") (pintype "passive"))
      (node (ref "R19") (pin "2") (pinfunction "2_2") (pintype "passive"))
    )
    (net (code "98") (name "Net-(LED8-PadA)") (class "Default")
      (node (ref "LED8") (pin "A") (pinfunction "A_A") (pintype "passive"))
      (node (ref "R20") (pin "2") (pinfunction "2_2") (pintype "passive"))
    )
    (net (code "99") (name "Net-(LED9-PadA)") (class "Default")
      (node (ref "LED9") (pin "A") (pinfunction "A_A") (pintype "passive"))
      (node (ref "R21") (pin "2") (pinfunction "2_2") (pintype "passive"))
    )
    (net (code "100") (name "Net-(LED10-PadA)") (class "Default")
      (node (ref "LED10") (pin "A") (pinfunction "A_A") (pintype "passive"))
      (node (ref "R22") (pin "2") (pinfunction "2_2") (pintype "passive"))
    )
    (net (code "101") (name "Net-(LED11-PadA)") (class "Default")
      (node (ref "LED11") (pin "A") (pinfunction "A_A") (pintype "passive"))
      (node (ref "R23") (pin "2") (pinfunction "2_2") (pintype "passive"))
    )
    (net (code "102") (name "Net-(LED12-PadA)") (class "Default")
      (node (ref "LED12") (pin "A") (pinfunction "A_A") (pintype "passive"))
      (node (ref "R24") (pin "2") (pinfunction "2_2") (pintype "passive"))
    )
    (net (code "103") (name "Net-(Q2-PadB)") (class "Default")
      (node (ref "Q2") (pin "B") (pinfunction "B_B") (pintype "passive"))
      (node (ref "R28") (pin "1") (pinfunction "1_1") (pintype "passive"))
      (node (ref "R29") (pin "2") (pinfunction "2_2") (pintype "passive"))
    )
    (net (code "104") (name "Net-(Q2-PadE)") (class "Default")
      (node (ref "Q2") (pin "E") (pinfunction "E_E") (pintype "passive"))
      (node (ref "R27") (pin "1") (pinfunction "1_1") (pintype "passive"))
    )
    (net (code "105") (name "Net-(Q3-D)") (class "Default")
      (node (ref "D1") (pin "A") (pinfunction "A_A") (pintype "passive"))
      (node (ref "JP2") (pin "2") (pinfunction "2_2") (pintype "passive"))
      (node (ref "Q3") (pin "3") (pinfunction "D_3") (pintype "passive"))
    )
    (net (code "106") (name "Net-(Q5-Pad1)") (class "Default")
      (node (ref "Q5") (pin "1") (pinfunction "1_1") (pintype "passive"))
      (node (ref "Q5") (pin "2") (pinfunction "2_2") (pintype "passive"))
      (node (ref "Q5") (pin "3") (pinfunction "3_3") (pintype "passive"))
      (node (ref "R36") (pin "1") (pinfunction "1_1") (pintype "passive"))
      (node (ref "R38") (pin "2") (pinfunction "2_2") (pintype "passive"))
      (node (ref "R39") (pin "2") (pinfunction "2_2") (pintype "passive"))
    )
    (net (code "107") (name "Net-(Q5-Pad4)") (class "Default")
      (node (ref "Q5") (pin "4") (pinfunction "4_4") (pintype "passive"))
      (node (ref "R39") (pin "1") (pinfunction "1_1") (pintype "passive"))
      (node (ref "R40") (pin "1") (pinfunction "1_1") (pintype "passive"))
    )
    (net (code "108") (name "Net-(Q5-Pad5)") (class "Default")
      (node (ref "Q5") (pin "5") (pinfunction "5_5") (pintype "passive"))
      (node (ref "Q5") (pin "6") (pinfunction "6_6") (pintype "passive"))
      (node (ref "Q5") (pin "7") (pinfunction "7_7") (pintype "passive"))
      (node (ref "Q5") (pin "8") (pinfunction "8_8") (pintype "passive"))
      (node (ref "Q6") (pin "5") (pinfunction "5_5") (pintype "passive"))
      (node (ref "Q6") (pin "6") (pinfunction "6_6") (pintype "passive"))
      (node (ref "Q6") (pin "7") (pinfunction "7_7") (pintype "passive"))
      (node (ref "Q6") (pin "8") (pinfunction "8_8") (pintype "passive"))
    )
    (net (code "109") (name "Net-(Q7-D)") (class "Default")
      (node (ref "Q7") (pin "3") (pinfunction "D_3") (pintype "passive"))
      (node (ref "R46") (pin "1") (pinfunction "1_1") (pintype "passive"))
    )
    (net (code "110") (name "Net-(R46-Pad2)") (class "Default")
      (node (ref "R46") (pin "2") (pinfunction "2_2") (pintype "passive"))
      (node (ref "R47") (pin "2") (pinfunction "2_2") (pintype "passive"))
      (node (ref "R48") (pin "1") (pinfunction "1_1") (pintype "passive"))
    )
    (net (code "111") (name "Net-(U$1-CLOCK16N)") (class "Default")
      (node (ref "Q4") (pin "1") (pinfunction "1_1") (pintype "passive"))
      (node (ref "U$1") (pin "20") (pinfunction "CLOCK16N_20") (pintype "bidirectional"))
    )
    (net (code "112") (name "Net-(U$1-CLOCK16P)") (class "Default")
      (node (ref "Q4") (pin "2") (pinfunction "2_2") (pintype "passive"))
      (node (ref "U$1") (pin "19") (pinfunction "CLOCK16P_19") (pintype "bidirectional"))
    )
    (net (code "113") (name "Net-(U$1-SYSCLK)") (class "Default")
      (node (ref "RF_SYSCLK") (pin "TP") (pinfunction "TP_TP") (pintype "input"))
      (node (ref "U$1") (pin "7") (pinfunction "SYSCLK_7") (pintype "output"))
    )
    (net (code "114") (name "Net-(U$1-VDD_IO)") (class "Default")
      (node (ref "B6") (pin "2") (pinfunction "2_2") (pintype "passive"))
      (node (ref "C24") (pin "2") (pinfunction "2_2") (pintype "passive"))
      (node (ref "U$1") (pin "15") (pinfunction "VDD_IO_15") (pintype "power_in"))
    )
    (net (code "115") (name "Net-(U$2-GATE_VOLTAGE)") (class "Default")
      (node (ref "B7") (pin "2") (pinfunction "2_2") (pintype "passive"))
      (node (ref "U$2") (pin "3") (pinfunction "GATE_VOLTAGE_3") (pintype "bidirectional"))
    )
    (net (code "116") (name "Net-(U$3-IFB)") (class "Default")
      (node (ref "C49") (pin "2") (pinfunction "2_2") (pintype "passive"))
      (node (ref "R48") (pin "2") (pinfunction "2_2") (pintype "passive"))
      (node (ref "R49") (pin "1") (pinfunction "1_1") (pintype "passive"))
      (node (ref "U$3") (pin "3") (pinfunction "IFB_3") (pintype "bidirectional"))
    )
    (net (code "117") (name "Net-(U$3-VC)") (class "Default")
      (node (ref "R45") (pin "1") (pinfunction "1_1") (pintype "passive"))
      (node (ref "U$3") (pin "1") (pinfunction "VC_1") (pintype "bidirectional"))
    )
    (net (code "118") (name "Net-(U$3-VFB)") (class "Default")
      (node (ref "R51") (pin "1") (pinfunction "1_1") (pintype "passive"))
      (node (ref "R52") (pin "2") (pinfunction "2_2") (pintype "passive"))
      (node (ref "U$3") (pin "2") (pinfunction "VFB_2") (pintype "bidirectional"))
    )
    (net (code "119") (name "Net-(U$3-VIN)") (class "Default")
      (node (ref "C48") (pin "+") (pinfunction "+_+") (pintype "passive"))
      (node (ref "J4") (pin "VBUS") (pinfunction "VBUS_VBUS") (pintype "power_in"))
      (node (ref "L8") (pin "1") (pinfunction "1_1") (pintype "passive"))
      (node (ref "U$3") (pin "7") (pinfunction "VIN_7") (pintype "bidirectional"))
    )
    (net (code "120") (name "Net-(U$3-VSW)") (class "Default")
      (node (ref "C63") (pin "+") (pinfunction "+_+") (pintype "passive"))
      (node (ref "L8") (pin "2") (pinfunction "2_2") (pintype "passive"))
      (node (ref "U$3") (pin "5") (pinfunction "VSW_5") (pintype "bidirectional"))
    )
    (net (code "121") (name "Net-(U2-PH0-OSC_IN)") (class "Default")
      (node (ref "C14") (pin "1") (pinfunction "1_1") (pintype "passive"))
      (node (ref "Q1") (pin "2") (pinfunction "2_2") (pintype "passive"))
      (node (ref "U2") (pin "5") (pinfunction "PH0-OSC_IN_5") (pintype "bidirectional"))
    )
    (net (code "122") (name "Net-(U2-PH1-OSC_OUT)") (class "Default")
      (node (ref "R9") (pin "2") (pinfunction "2_2") (pintype "passive"))
      (node (ref "U2") (pin "6") (pinfunction "PH1-OSC_OUT_6") (pintype "bidirectional"))
    )
    (net (code "123") (name "Net-(U3-D+)") (class "Default")
      (node (ref "J1") (pin "D+") (pinfunction "D+_D+") (pintype "bidirectional"))
      (node (ref "U3") (pin "19") (pinfunction "D+_19") (pintype "bidirectional"))
    )
    (net (code "124") (name "Net-(U3-D-)") (class "Default")
      (node (ref "J1") (pin "D-") (pinfunction "D-_D-") (pintype "bidirectional"))
      (node (ref "U3") (pin "18") (pinfunction "D-_18") (pintype "bidirectional"))
    )
    (net (code "125") (name "Net-(U3-GP6{slash}RXLED)") (class "Default")
      (node (ref "LED11") (pin "C") (pinfunction "C_C") (pintype "passive"))
      (node (ref "U3") (pin "6") (pinfunction "GP6/RXLED_6") (pintype "bidirectional"))
    )
    (net (code "126") (name "Net-(U3-GP7{slash}TXLED)") (class "Default")
      (node (ref "LED12") (pin "C") (pinfunction "C_C") (pintype "passive"))
      (node (ref "U3") (pin "5") (pinfunction "GP7/TXLED_5") (pintype "bidirectional"))
    )
    (net (code "127") (name "Net-(U3-VUSB)") (class "Default")
      (node (ref "C20") (pin "1") (pinfunction "1_1") (pintype "passive"))
      (node (ref "U3") (pin "17") (pinfunction "VUSB_17") (pintype "power_in"))
    )
    (net (code "128") (name "Net-(U4-IO3)") (class "Default")
      (node (ref "J2") (pin "ID") (pinfunction "ID_ID") (pintype "bidirectional"))
      (node (ref "R26") (pin "1") (pinfunction "1_1") (pintype "passive"))
      (node (ref "U4") (pin "4") (pinfunction "IO3_4") (pintype "bidirectional"))
    )
    (net (code "129") (name "Net-(U5-AVDD)") (class "Default")
      (node (ref "C42") (pin "2") (pinfunction "2_2") (pintype "passive"))
      (node (ref "U5") (pin "17") (pinfunction "CCFG_17") (pintype "bidirectional"))
      (node (ref "U5") (pin "2") (pinfunction "AVDD_2") (pintype "bidirectional"))
    )
    (net (code "130") (name "Net-(U5-AVSS)") (class "Default")
      (node (ref "BAT") (pin "5") (pinfunction "5_5") (pintype "passive"))
      (node (ref "C38") (pin "2") (pinfunction "2_2") (pintype "passive"))
      (node (ref "C39") (pin "2") (pinfunction "2_2") (pintype "passive"))
      (node (ref "C40") (pin "2") (pinfunction "2_2") (pintype "passive"))
      (node (ref "C41") (pin "2") (pinfunction "2_2") (pintype "passive"))
      (node (ref "C42") (pin "1") (pinfunction "1_1") (pintype "passive"))
      (node (ref "C43") (pin "2") (pinfunction "2_2") (pintype "passive"))
      (node (ref "C44") (pin "1") (pinfunction "1_1") (pintype "passive"))
      (node (ref "C46") (pin "2") (pinfunction "2_2") (pintype "passive"))
      (node (ref "R36") (pin "2") (pinfunction "2_2") (pintype "passive"))
      (node (ref "R37") (pin "2") (pinfunction "2_2") (pintype "passive"))
      (node (ref "R62") (pin "2") (pinfunction "2_2") (pintype "passive"))
      (node (ref "U5") (pin "18") (pinfunction "CTRC_18") (pintype "bidirectional"))
      (node (ref "U5") (pin "19") (pinfunction "CTRD_19") (pintype "bidirectional"))
      (node (ref "U5") (pin "20") (pinfunction "DVSS_20") (pintype "bidirectional"))
      (node (ref "U5") (pin "8") (pinfunction "AVSS_8") (pintype "bidirectional"))
    )
    (net (code "131") (name "Net-(U5-CHG)") (class "Default")
      (node (ref "R43") (pin "1") (pinfunction "1_1") (pintype "passive"))
      (node (ref "U5") (pin "13") (pinfunction "CHG_13") (pintype "bidirectional"))
    )
    (net (code "132") (name "Net-(U5-DSG)") (class "Default")
      (node (ref "R40") (pin "2") (pinfunction "2_2") (pintype "passive"))
      (node (ref "U5") (pin "11") (pinfunction "DSG_11") (pintype "bidirectional"))
    )
    (net (code "133") (name "Net-(U5-LD)") (class "Default")
      (node (ref "R44") (pin "1") (pinfunction "1_1") (pintype "passive"))
      (node (ref "U5") (pin "14") (pinfunction "LD_14") (pintype "bidirectional"))
    )
    (net (code "134") (name "Net-(U5-SRN)") (class "Default")
      (node (ref "C45") (pin "2") (pinfunction "2_2") (pintype "passive"))
      (node (ref "C46") (pin "1") (pinfunction "1_1") (pintype "passive"))
      (node (ref "R38") (pin "1") (pinfunction "1_1") (pintype "passive"))
      (node (ref "U5") (pin "10") (pinfunction "SRN_10") (pintype "bidirectional"))
    )
    (net (code "135") (name "Net-(U5-SRP)") (class "Default")
      (node (ref "C44") (pin "2") (pinfunction "2_2") (pintype "passive"))
      (node (ref "C45") (pin "1") (pinfunction "1_1") (pintype "passive"))
      (node (ref "R37") (pin "1") (pinfunction "1_1") (pintype "passive"))
      (node (ref "U5") (pin "9") (pinfunction "SRP_9") (pintype "bidirectional"))
    )
    (net (code "136") (name "Net-(U5-TS)") (class "Default")
      (node (ref "R35") (pin "2") (pinfunction "2_2") (pintype "passive"))
      (node (ref "R62") (pin "1") (pinfunction "1_1") (pintype "passive"))
      (node (ref "U5") (pin "15") (pinfunction "TS_15") (pintype "bidirectional"))
    )
    (net (code "137") (name "Net-(U5-VC1)") (class "Default")
      (node (ref "C39") (pin "1") (pinfunction "1_1") (pintype "passive"))
      (node (ref "R33") (pin "2") (pinfunction "2_2") (pintype "passive"))
      (node (ref "U5") (pin "7") (pinfunction "VC1_7") (pintype "bidirectional"))
    )
    (net (code "138") (name "Net-(U5-VC2)") (class "Default")
      (node (ref "C40") (pin "1") (pinfunction "1_1") (pintype "passive"))
      (node (ref "R32") (pin "2") (pinfunction "2_2") (pintype "passive"))
      (node (ref "U5") (pin "6") (pinfunction "VC2_6") (pintype "bidirectional"))
    )
    (net (code "139") (name "Net-(U5-VC3)") (class "Default")
      (node (ref "C41") (pin "1") (pinfunction "1_1") (pintype "passive"))
      (node (ref "R31") (pin "2") (pinfunction "2_2") (pintype "passive"))
      (node (ref "U5") (pin "5") (pinfunction "VC3_5") (pintype "bidirectional"))
    )
    (net (code "140") (name "Net-(U5-VC4)") (class "Default")
      (node (ref "C38") (pin "1") (pinfunction "1_1") (pintype "passive"))
      (node (ref "R30") (pin "2") (pinfunction "2_2") (pintype "passive"))
      (node (ref "U5") (pin "3") (pinfunction "VC5_3") (pintype "bidirectional"))
      (node (ref "U5") (pin "4") (pinfunction "VC4_4") (pintype "bidirectional"))
    )
    (net (code "141") (name "Net-(U5-VDD)") (class "Default")
      (node (ref "C43") (pin "1") (pinfunction "1_1") (pintype "passive"))
      (node (ref "R34") (pin "2") (pinfunction "2_2") (pintype "passive"))
      (node (ref "U5") (pin "1") (pinfunction "VDD_1") (pintype "bidirectional"))
    )
    (net (code "142") (name "Net-(U5-VTB)") (class "Default")
      (node (ref "R35") (pin "1") (pinfunction "1_1") (pintype "passive"))
      (node (ref "U5") (pin "16") (pinfunction "VTB_16") (pintype "bidirectional"))
    )
    (net (code "143") (name "unconnected-(D8-PadA)") (class "Default")
      (node (ref "D8") (pin "A") (pinfunction "A_A") (pintype "passive"))
    )
    (net (code "144") (name "unconnected-(D9-PadA)") (class "Default")
      (node (ref "D9") (pin "A") (pinfunction "A_A") (pintype "passive"))
    )
    (net (code "145") (name "unconnected-(IC2-BK_O-Pad10)") (class "Default")
      (node (ref "IC2") (pin "10") (pinfunction "BK_O_10") (pintype "bidirectional"))
    )
    (net (code "146") (name "unconnected-(IC2-NC-Pad20)") (class "Default")
      (node (ref "IC2") (pin "20") (pinfunction "NC_20") (pintype "no_connect"))
    )
    (net (code "147") (name "unconnected-(IC2-P0_0{slash}CTS-Pad15)") (class "Default")
      (node (ref "IC2") (pin "15") (pinfunction "P0_0/CTS_15") (pintype "bidirectional"))
    )
    (net (code "148") (name "unconnected-(IC2-P0_7-Pad29)") (class "Default")
      (node (ref "IC2") (pin "29") (pinfunction "P0_7_29") (pintype "bidirectional"))
    )
    (net (code "149") (name "unconnected-(IC2-P1_0-Pad16)") (class "Default")
      (node (ref "IC2") (pin "16") (pinfunction "P1_0_16") (pintype "bidirectional"))
    )
    (net (code "150") (name "unconnected-(IC2-P1_1-Pad12)") (class "Default")
      (node (ref "IC2") (pin "12") (pinfunction "P1_1_12") (pintype "bidirectional"))
    )
    (net (code "151") (name "unconnected-(IC2-P1_2{slash}SCL-Pad13)") (class "Default")
      (node (ref "IC2") (pin "13") (pinfunction "P1_2/SCL_13") (pintype "bidirectional"))
    )
    (net (code "152") (name "unconnected-(IC2-P1_3{slash}SDA-Pad14)") (class "Default")
      (node (ref "IC2") (pin "14") (pinfunction "P1_3/SDA_14") (pintype "bidirectional"))
    )
    (net (code "153") (name "unconnected-(IC2-P2_2-Pad5)") (class "Default")
      (node (ref "IC2") (pin "5") (pinfunction "P2_2_5") (pintype "bidirectional"))
    )
    (net (code "154") (name "unconnected-(IC2-P2_3-Pad9)") (class "Default")
      (node (ref "IC2") (pin "9") (pinfunction "P2_3_9") (pintype "bidirectional"))
    )
    (net (code "155") (name "unconnected-(IC2-P2_4-Pad19)") (class "Default")
      (node (ref "IC2") (pin "19") (pinfunction "P2_4_19") (pintype "bidirectional"))
    )
    (net (code "156") (name "unconnected-(IC2-P2_7{slash}TX_IND-Pad11)") (class "Default")
      (node (ref "IC2") (pin "11") (pinfunction "P2_7/TX_IND_11") (pintype "bidirectional"))
    )
    (net (code "157") (name "unconnected-(IC2-P3_1-Pad24)") (class "Default")
      (node (ref "IC2") (pin "24") (pinfunction "P3_1_24") (pintype "bidirectional"))
    )
    (net (code "158") (name "unconnected-(IC2-P3_2-Pad25)") (class "Default")
      (node (ref "IC2") (pin "25") (pinfunction "P3_2_25") (pintype "bidirectional"))
    )
    (net (code "159") (name "unconnected-(IC2-P3_3-Pad26)") (class "Default")
      (node (ref "IC2") (pin "26") (pinfunction "P3_3_26") (pintype "bidirectional"))
    )
    (net (code "160") (name "unconnected-(IC2-P3_4-Pad27)") (class "Default")
      (node (ref "IC2") (pin "27") (pinfunction "P3_4_27") (pintype "bidirectional"))
    )
    (net (code "161") (name "unconnected-(IC2-P3_5-Pad28)") (class "Default")
      (node (ref "IC2") (pin "28") (pinfunction "P3_5_28") (pintype "bidirectional"))
    )
    (net (code "162") (name "unconnected-(IC2-P3_6{slash}RTS-Pad17)") (class "Default")
      (node (ref "IC2") (pin "17") (pinfunction "P3_6/RTS_17") (pintype "bidirectional"))
    )
    (net (code "163") (name "unconnected-(IC2-ULC_O-Pad8)") (class "Default")
      (node (ref "IC2") (pin "8") (pinfunction "ULC_O_8") (pintype "bidirectional"))
    )
    (net (code "164") (name "unconnected-(IC2-VDD_IO(1)-Pad6)") (class "Default")
      (node (ref "IC2") (pin "6") (pinfunction "VDD_IO(1)_6") (pintype "bidirectional"))
    )
    (net (code "165") (name "unconnected-(IC2-VDD_IO(2)-Pad7)") (class "Default")
      (node (ref "IC2") (pin "7") (pinfunction "VDD_IO(2)_7") (pintype "bidirectional"))
    )
    (net (code "166") (name "unconnected-(J1-PadID)") (class "Default")
      (node (ref "J1") (pin "ID") (pinfunction "ID_ID") (pintype "bidirectional"))
    )
    (net (code "167") (name "unconnected-(U$1-NC1-Pad5)") (class "Default")
      (node (ref "U$1") (pin "5") (pinfunction "NC1_5") (pintype "no_connect"))
    )
    (net (code "168") (name "unconnected-(U$1-NC2-Pad6)") (class "Default")
      (node (ref "U$1") (pin "6") (pinfunction "NC2_6") (pintype "no_connect"))
    )
    (net (code "169") (name "unconnected-(U$1-NC3-Pad11)") (class "Default")
      (node (ref "U$1") (pin "11") (pinfunction "NC3_11") (pintype "no_connect"))
    )
    (net (code "170") (name "unconnected-(U$1-NC4-Pad13)") (class "Default")
      (node (ref "U$1") (pin "13") (pinfunction "NC4_13") (pintype "no_connect"))
    )
    (net (code "171") (name "unconnected-(U$1-NC5-Pad16)") (class "Default")
      (node (ref "U$1") (pin "16") (pinfunction "NC5_16") (pintype "no_connect"))
    )
    (net (code "172") (name "unconnected-(U$1-NC6-Pad18)") (class "Default")
      (node (ref "U$1") (pin "18") (pinfunction "NC6_18") (pintype "no_connect"))
    )
    (net (code "173") (name "unconnected-(U2-PB3-Pad55)") (class "Default")
      (node (ref "U2") (pin "55") (pinfunction "PB3_55") (pintype "bidirectional"))
    )
    (net (code "174") (name "unconnected-(U2-PB4-Pad56)") (class "Default")
      (node (ref "U2") (pin "56") (pinfunction "PB4_56") (pintype "bidirectional"))
    )
    (net (code "175") (name "unconnected-(U2-PB5-Pad57)") (class "Default")
      (node (ref "U2") (pin "57") (pinfunction "PB5_57") (pintype "bidirectional"))
    )
    (net (code "176") (name "unconnected-(U2-PB6-Pad58)") (class "Default")
      (node (ref "U2") (pin "58") (pinfunction "PB6_58") (pintype "bidirectional"))
    )
    (net (code "177") (name "unconnected-(U2-PB7-Pad59)") (class "Default")
      (node (ref "U2") (pin "59") (pinfunction "PB7_59") (pintype "bidirectional"))
    )
    (net (code "178") (name "unconnected-(U2-PB8-Pad61)") (class "Default")
      (node (ref "U2") (pin "61") (pinfunction "PB8_61") (pintype "bidirectional"))
    )
    (net (code "179") (name "unconnected-(U2-PB9-Pad62)") (class "Default")
      (node (ref "U2") (pin "62") (pinfunction "PB9_62") (pintype "bidirectional"))
    )
    (net (code "180") (name "unconnected-(U2-PC13-Pad2)") (class "Default")
      (node (ref "U2") (pin "2") (pinfunction "PC13_2") (pintype "bidirectional"))
    )
    (net (code "181") (name "unconnected-(U2-PC14-OSC32_IN-Pad3)") (class "Default")
      (node (ref "U2") (pin "3") (pinfunction "PC14-OSC32_IN_3") (pintype "bidirectional"))
    )
    (net (code "182") (name "unconnected-(U2-PC15-OSC32_OUT-Pad4)") (class "Default")
      (node (ref "U2") (pin "4") (pinfunction "PC15-OSC32_OUT_4") (pintype "bidirectional"))
    )
    (net (code "183") (name "unconnected-(U3-GP0{slash}SSPND-Pad16)") (class "Default")
      (node (ref "U3") (pin "16") (pinfunction "GP0/SSPND_16") (pintype "bidirectional"))
    )
    (net (code "184") (name "unconnected-(U3-GP1{slash}USBCFG-Pad15)") (class "Default")
      (node (ref "U3") (pin "15") (pinfunction "GP1/USBCFG_15") (pintype "bidirectional"))
    )
    (net (code "185") (name "unconnected-(U3-GP2-Pad14)") (class "Default")
      (node (ref "U3") (pin "14") (pinfunction "GP2_14") (pintype "bidirectional"))
    )
    (net (code "186") (name "unconnected-(U3-GP3-Pad9)") (class "Default")
      (node (ref "U3") (pin "9") (pinfunction "GP3_9") (pintype "bidirectional"))
    )
    (net (code "187") (name "unconnected-(U3-GP4-Pad8)") (class "Default")
      (node (ref "U3") (pin "8") (pinfunction "GP4_8") (pintype "bidirectional"))
    )
    (net (code "188") (name "unconnected-(U3-GP5-Pad7)") (class "Default")
      (node (ref "U3") (pin "7") (pinfunction "GP5_7") (pintype "bidirectional"))
    )
    (net (code "189") (name "unconnected-(U3-N_CTS-Pad13)") (class "Default")
      (node (ref "U3") (pin "13") (pinfunction "N_CTS_13") (pintype "input"))
    )
    (net (code "190") (name "unconnected-(U3-N_RTS-Pad11)") (class "Default")
      (node (ref "U3") (pin "11") (pinfunction "N_RTS_11") (pintype "output"))
    )
    (net (code "191") (name "unconnected-(U5-CHGU-Pad12)") (class "Default")
      (node (ref "U5") (pin "12") (pinfunction "CHGU_12") (pintype "bidirectional"))
    )
  )
)
